# A314v1.net
KiCad netlist of a schematic drawn in EAGLE
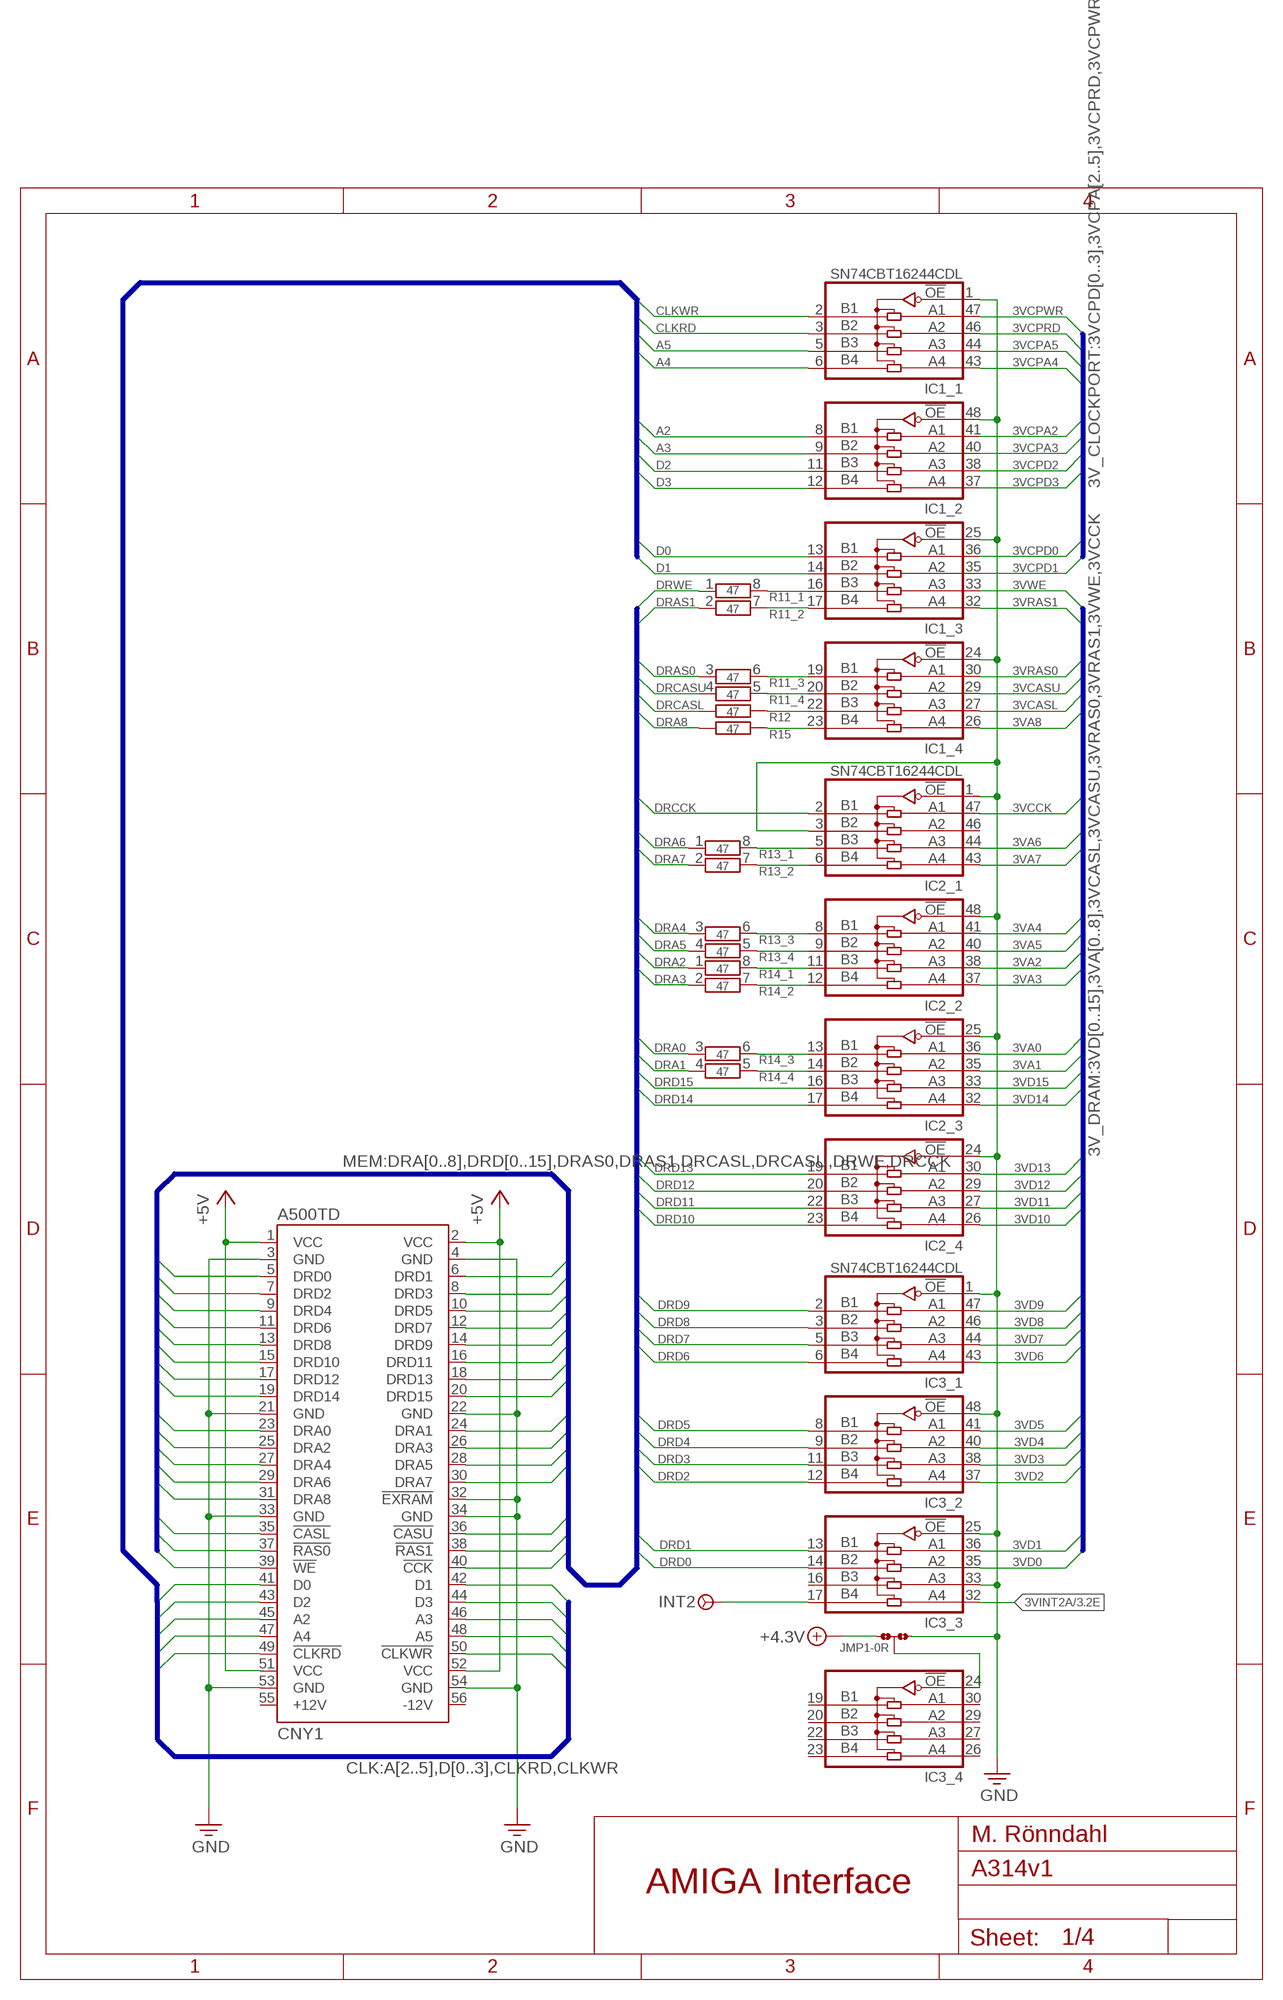
[diagram p0: schematic, sheet 1]
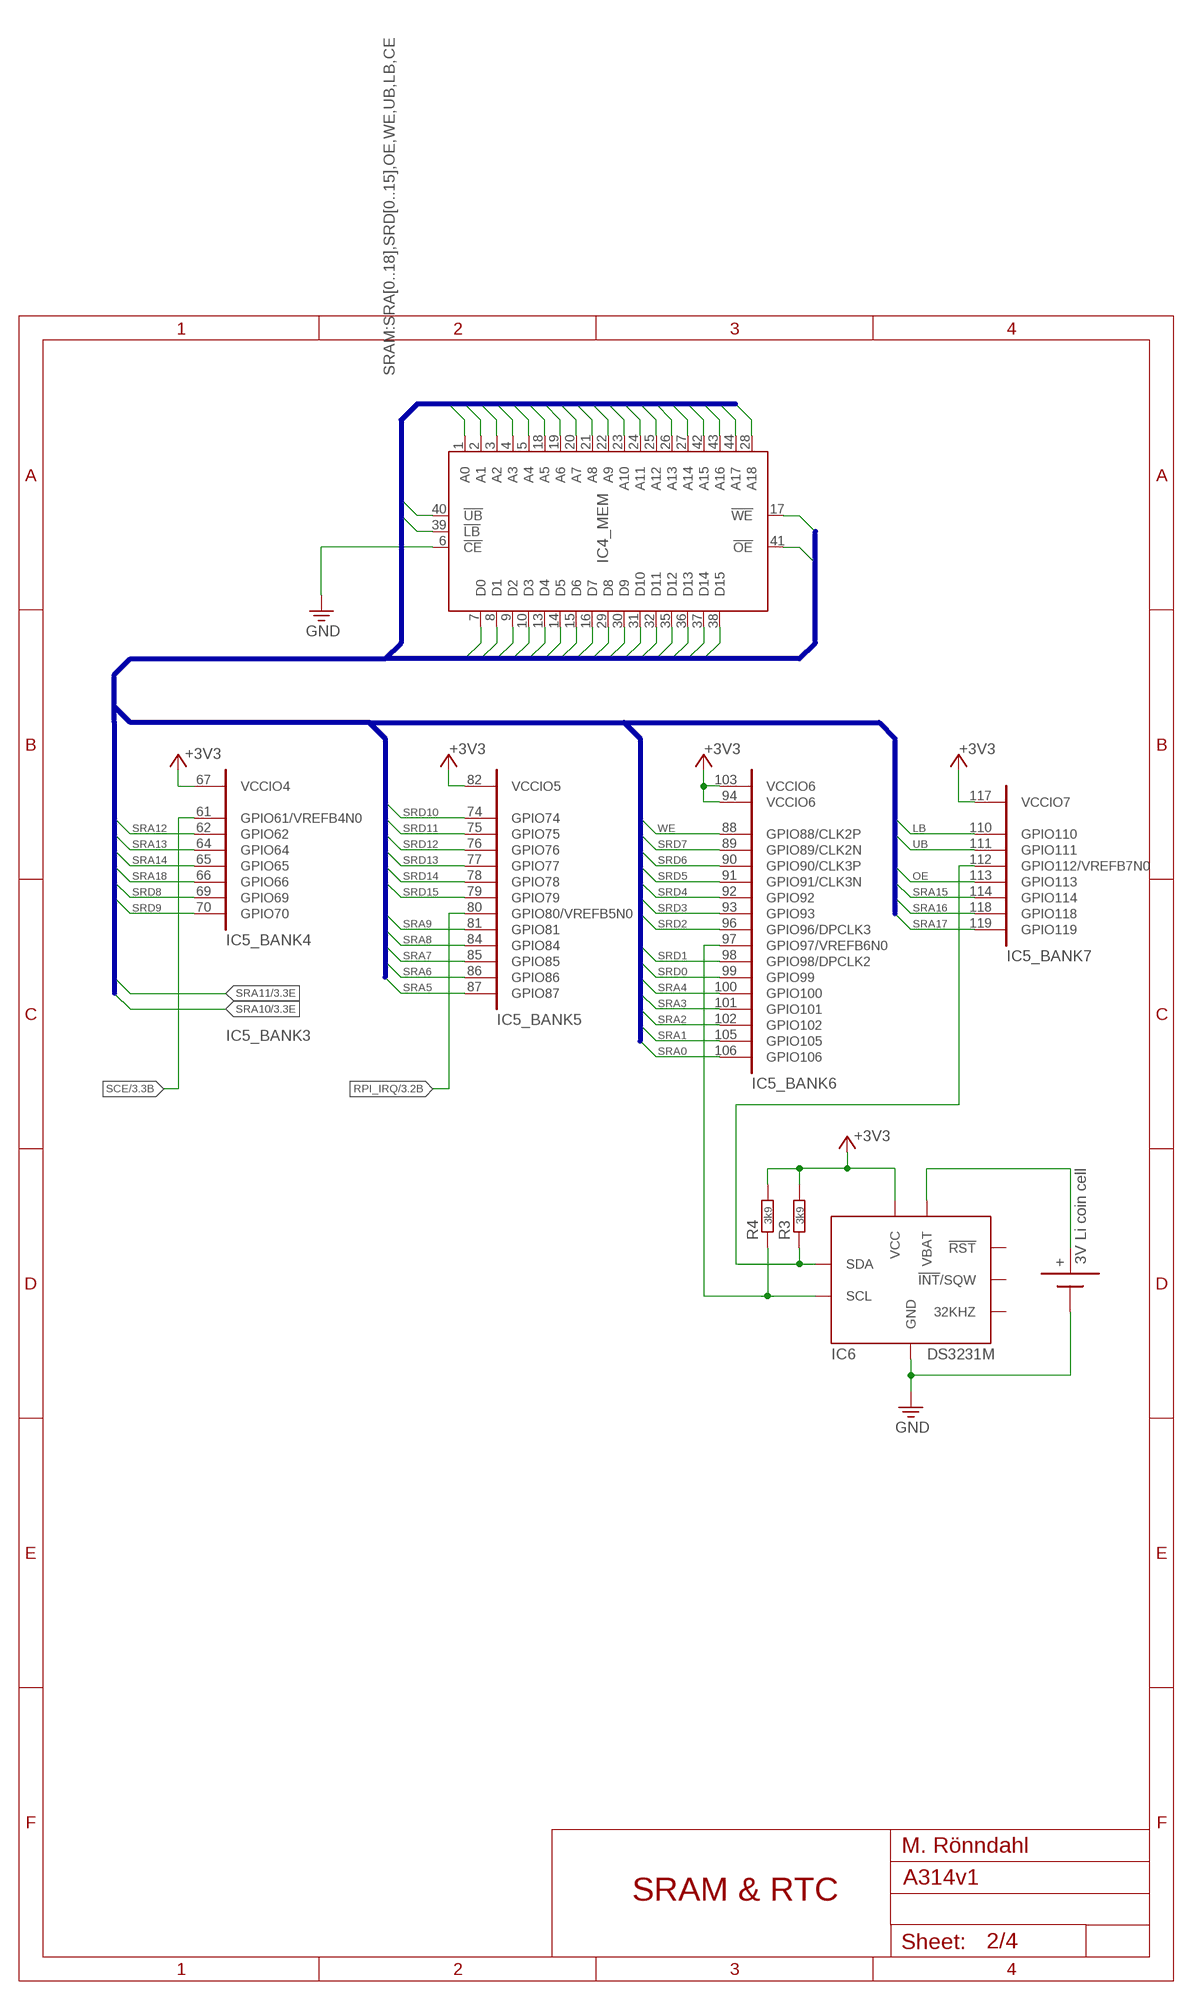
[diagram p1: schematic, sheet 2]
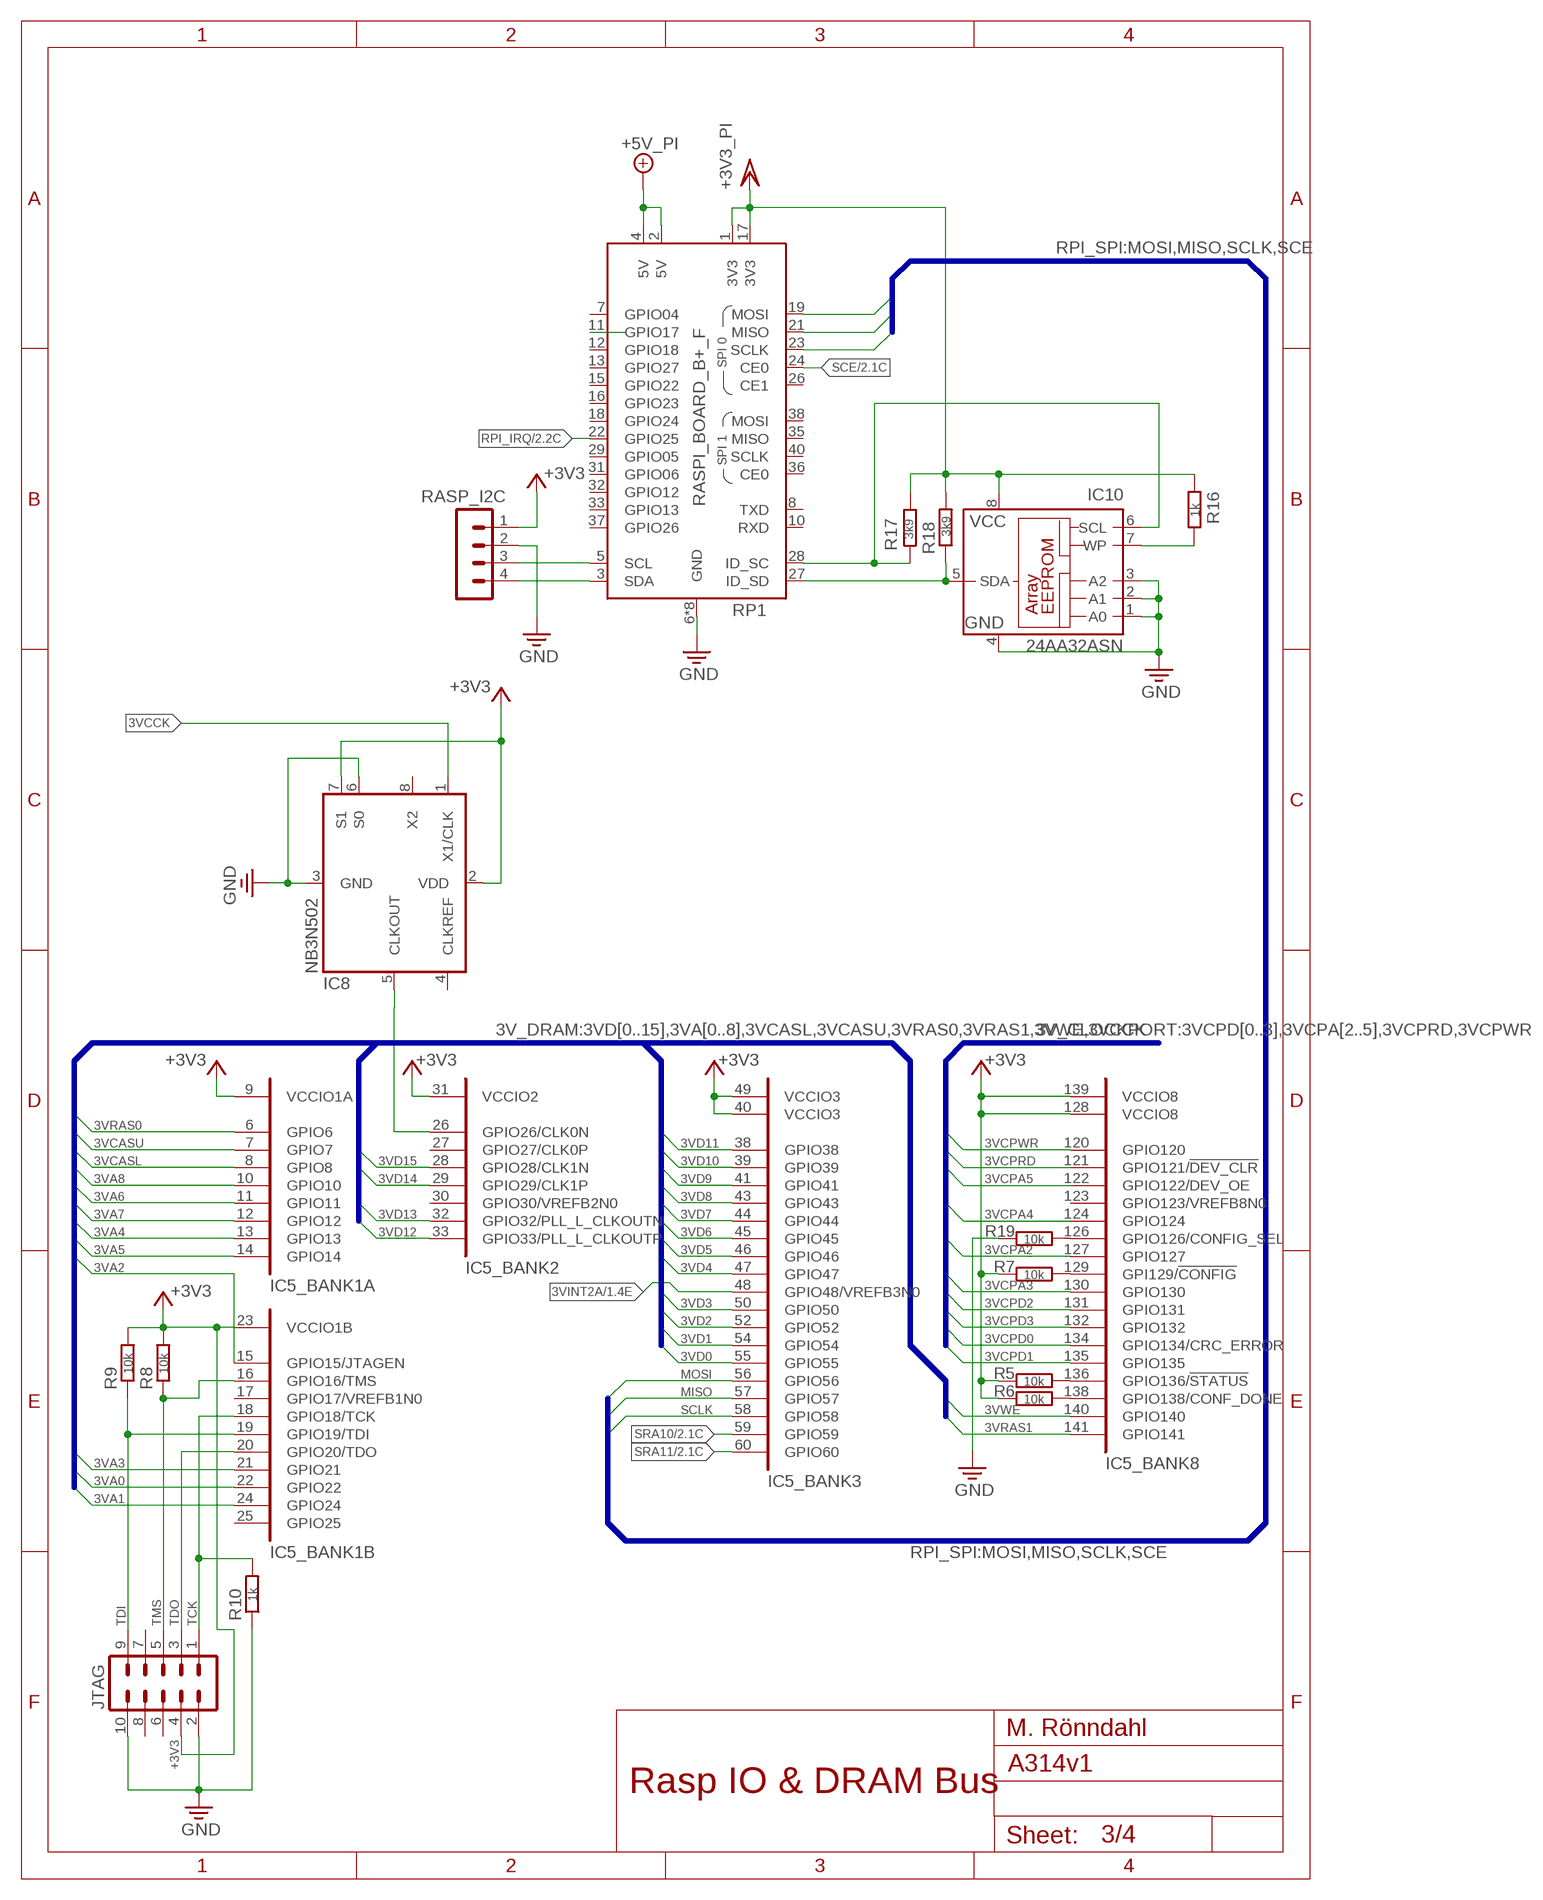
[diagram p2: schematic, sheet 3]
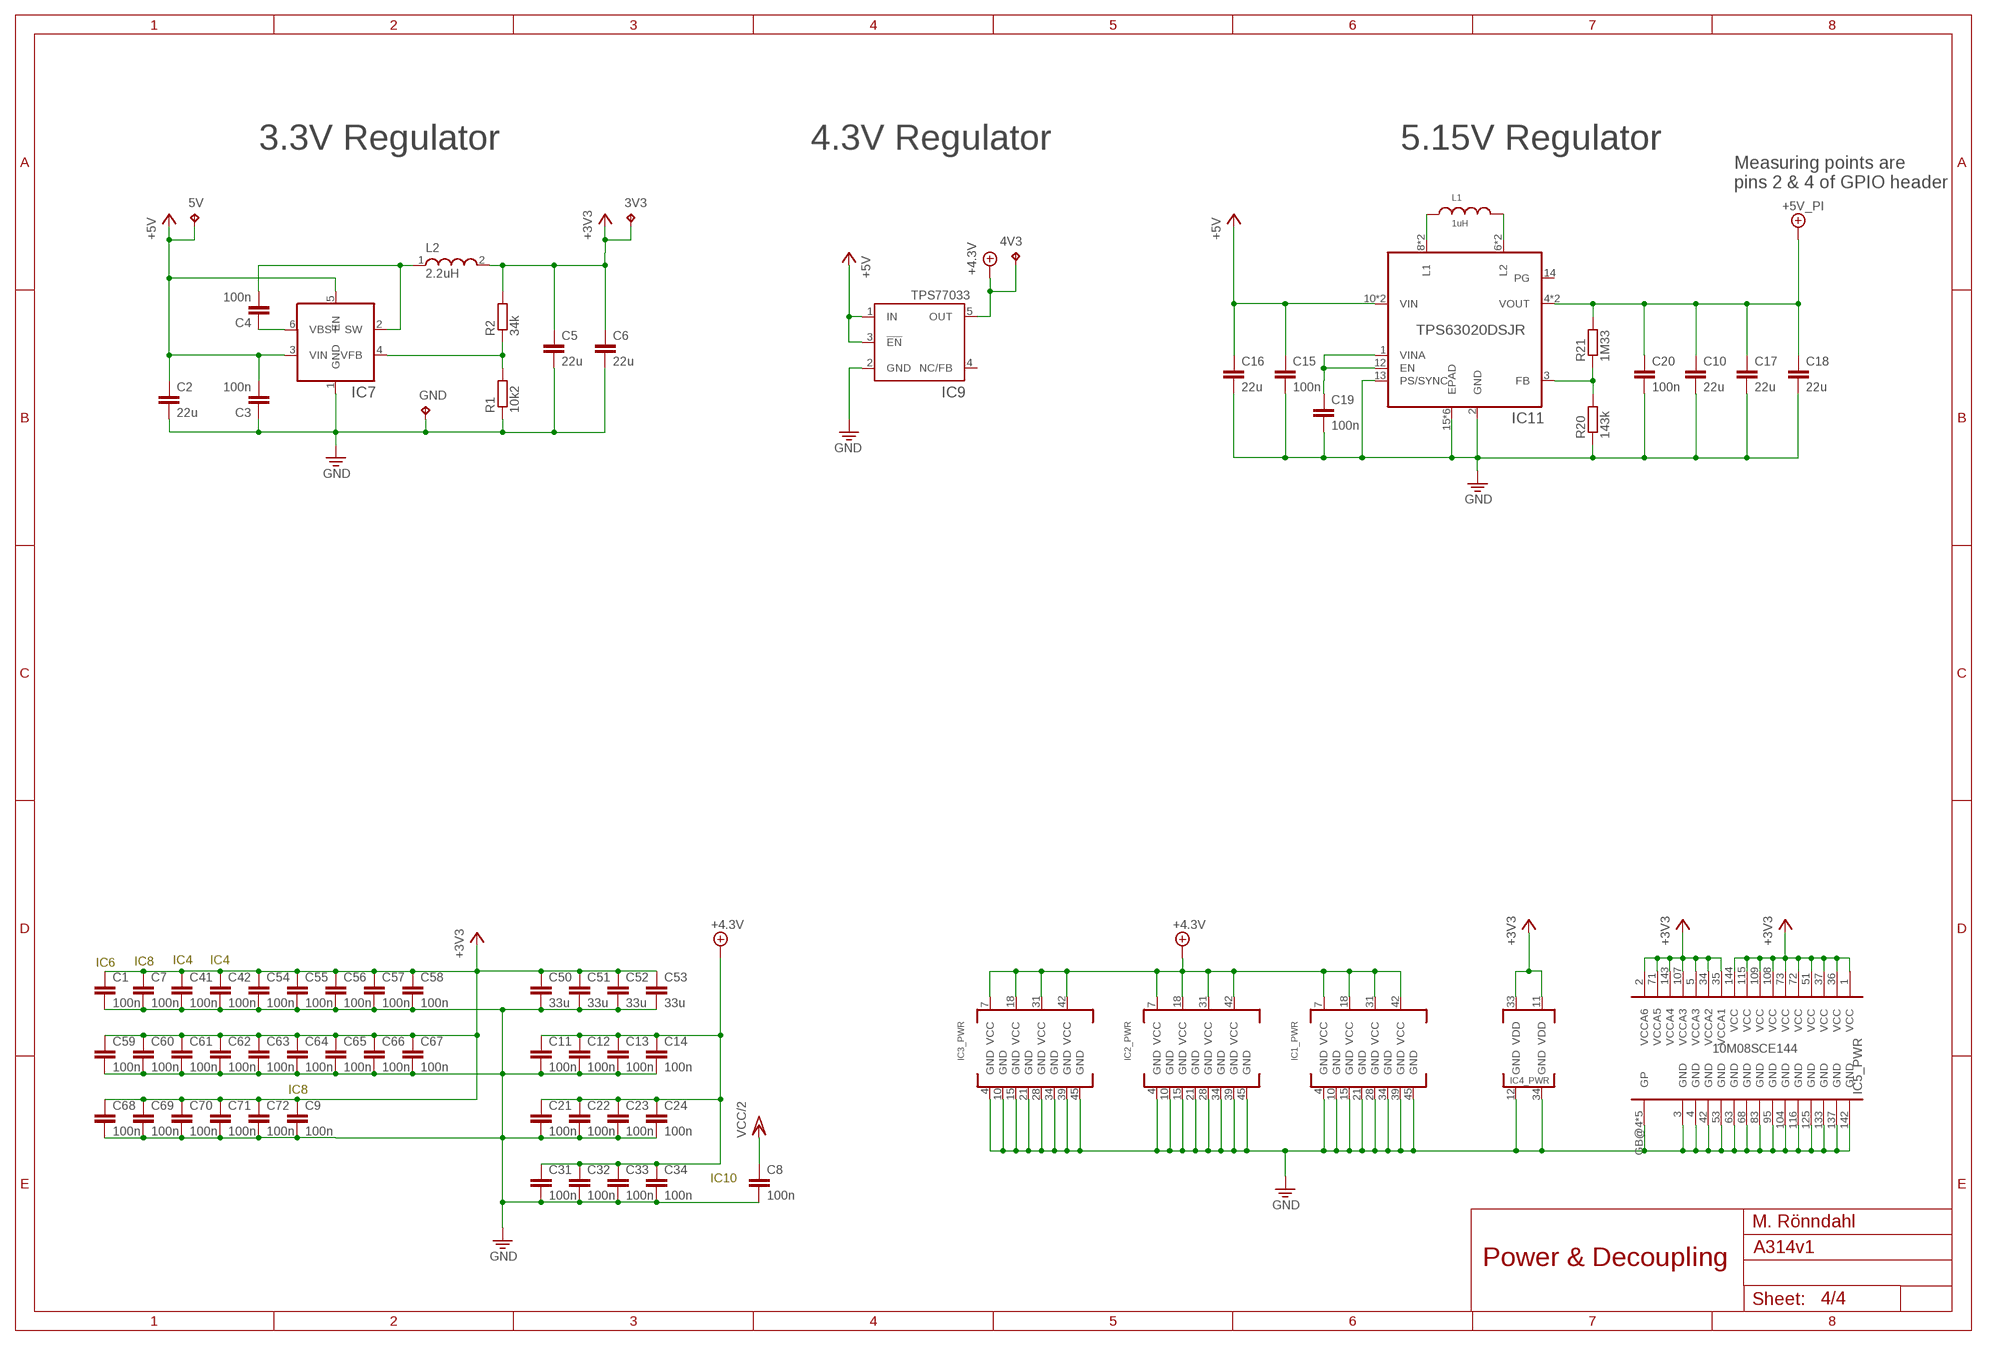
[diagram p3: schematic, sheet 4]

(export (version "E")
  (design (tool "Eeschema 10.0.6"))
  (components
    (comp (ref "CNY1")
      (value "A500TD")
      (footprint "eagle-import:TRAPDOOR")
      (libsource (lib "eagle-import") (part "A500TD"))
    )
    (comp (ref "IC1")
      (value "SN74CBT16244CDL")
      (footprint "eagle-import:SSOP-DL48")
      (libsource (lib "eagle-import") (part "SN74CBT16244CDL"))
    )
    (comp (ref "IC2")
      (value "SN74CBT16244CDL")
      (footprint "eagle-import:SSOP-DL48")
      (libsource (lib "eagle-import") (part "SN74CBT16244CDL"))
    )
    (comp (ref "IC3")
      (value "SN74CBT16244CDL")
      (footprint "eagle-import:SSOP-DL48")
      (libsource (lib "eagle-import") (part "SN74CBT16244CDL"))
    )
    (comp (ref "INT2")
      (value "TP1")
      (footprint "eagle-import:P1-08")
      (libsource (lib "eagle-import") (part "TP_LITE"))
    )
    (comp (ref "JMP1")
      (value "0R-JUMPC")
      (footprint "eagle-import:C0R-JMP")
      (libsource (lib "eagle-import") (part "0R-JUMPC"))
    )
    (comp (ref "R11")
      (value "47")
      (footprint "eagle-import:CTS742C083")
      (libsource (lib "eagle-import") (part "CTS742C083_S"))
    )
    (comp (ref "R12")
      (value "47")
      (footprint "eagle-import:R0805")
      (libsource (lib "eagle-import") (part "R-EU_R0805"))
    )
    (comp (ref "R13")
      (value "47")
      (footprint "eagle-import:CTS742C083")
      (libsource (lib "eagle-import") (part "CTS742C083_S"))
    )
    (comp (ref "R14")
      (value "47")
      (footprint "eagle-import:CTS742C083")
      (libsource (lib "eagle-import") (part "CTS742C083_S"))
    )
    (comp (ref "R15")
      (value "47")
      (footprint "eagle-import:R0805")
      (libsource (lib "eagle-import") (part "R-EU_R0805"))
    )
    (comp (ref "3V3")
      (value "TPPAD1-13")
      (footprint "eagle-import:P1-13")
      (libsource (lib "eagle-import") (part "TPPAD1-13"))
    )
    (comp (ref "4V3")
      (value "TPPAD1-13")
      (footprint "eagle-import:P1-13")
      (libsource (lib "eagle-import") (part "TPPAD1-13"))
    )
    (comp (ref "5V")
      (value "TPPAD1-13")
      (footprint "eagle-import:P1-13")
      (libsource (lib "eagle-import") (part "TPPAD1-13"))
    )
    (comp (ref "C1")
      (value "100n")
      (footprint "eagle-import:C0805")
      (libsource (lib "eagle-import") (part "C-EUC0805"))
    )
    (comp (ref "C2")
      (value "22u")
      (footprint "eagle-import:C1812K")
      (libsource (lib "eagle-import") (part "C-EUC1812K"))
    )
    (comp (ref "C3")
      (value "100n")
      (footprint "eagle-import:C0805")
      (libsource (lib "eagle-import") (part "C-EUC0805"))
    )
    (comp (ref "C4")
      (value "100n")
      (footprint "eagle-import:C0805")
      (libsource (lib "eagle-import") (part "C-EUC0805"))
    )
    (comp (ref "C5")
      (value "22u")
      (footprint "eagle-import:C1812K")
      (libsource (lib "eagle-import") (part "C-EUC1812K"))
    )
    (comp (ref "C6")
      (value "22u")
      (footprint "eagle-import:C1812K")
      (libsource (lib "eagle-import") (part "C-EUC1812K"))
    )
    (comp (ref "C7")
      (value "100n")
      (footprint "eagle-import:C0805")
      (libsource (lib "eagle-import") (part "C-EUC0805"))
    )
    (comp (ref "C8")
      (value "100n")
      (footprint "eagle-import:C0805")
      (libsource (lib "eagle-import") (part "C-EUC0805"))
    )
    (comp (ref "C9")
      (value "100n")
      (footprint "eagle-import:C0805")
      (libsource (lib "eagle-import") (part "C-EUC0805"))
    )
    (comp (ref "C10")
      (value "22u")
      (footprint "eagle-import:C1812K")
      (libsource (lib "eagle-import") (part "C-EUC1812K"))
    )
    (comp (ref "C11")
      (value "100n")
      (footprint "eagle-import:C0805")
      (libsource (lib "eagle-import") (part "C-EUC0805"))
    )
    (comp (ref "C12")
      (value "100n")
      (footprint "eagle-import:C0805")
      (libsource (lib "eagle-import") (part "C-EUC0805"))
    )
    (comp (ref "C13")
      (value "100n")
      (footprint "eagle-import:C0805")
      (libsource (lib "eagle-import") (part "C-EUC0805"))
    )
    (comp (ref "C14")
      (value "100n")
      (footprint "eagle-import:C0805")
      (libsource (lib "eagle-import") (part "C-EUC0805"))
    )
    (comp (ref "C15")
      (value "100n")
      (footprint "eagle-import:C0805")
      (libsource (lib "eagle-import") (part "C-EUC0805"))
    )
    (comp (ref "C16")
      (value "22u")
      (footprint "eagle-import:C1812K")
      (libsource (lib "eagle-import") (part "C-EUC1812K"))
    )
    (comp (ref "C17")
      (value "22u")
      (footprint "eagle-import:C1812K")
      (libsource (lib "eagle-import") (part "C-EUC1812K"))
    )
    (comp (ref "C18")
      (value "22u")
      (footprint "eagle-import:C1812K")
      (libsource (lib "eagle-import") (part "C-EUC1812K"))
    )
    (comp (ref "C19")
      (value "100n")
      (footprint "eagle-import:C0805")
      (libsource (lib "eagle-import") (part "C-EUC0805"))
    )
    (comp (ref "C20")
      (value "100n")
      (footprint "eagle-import:C0805")
      (libsource (lib "eagle-import") (part "C-EUC0805"))
    )
    (comp (ref "C21")
      (value "100n")
      (footprint "eagle-import:C0805")
      (libsource (lib "eagle-import") (part "C-EUC0805"))
    )
    (comp (ref "C22")
      (value "100n")
      (footprint "eagle-import:C0805")
      (libsource (lib "eagle-import") (part "C-EUC0805"))
    )
    (comp (ref "C23")
      (value "100n")
      (footprint "eagle-import:C0805")
      (libsource (lib "eagle-import") (part "C-EUC0805"))
    )
    (comp (ref "C24")
      (value "100n")
      (footprint "eagle-import:C0805")
      (libsource (lib "eagle-import") (part "C-EUC0805"))
    )
    (comp (ref "C31")
      (value "100n")
      (footprint "eagle-import:C0805")
      (libsource (lib "eagle-import") (part "C-EUC0805"))
    )
    (comp (ref "C32")
      (value "100n")
      (footprint "eagle-import:C0805")
      (libsource (lib "eagle-import") (part "C-EUC0805"))
    )
    (comp (ref "C33")
      (value "100n")
      (footprint "eagle-import:C0805")
      (libsource (lib "eagle-import") (part "C-EUC0805"))
    )
    (comp (ref "C34")
      (value "100n")
      (footprint "eagle-import:C0805")
      (libsource (lib "eagle-import") (part "C-EUC0805"))
    )
    (comp (ref "C41")
      (value "100n")
      (footprint "eagle-import:C0805")
      (libsource (lib "eagle-import") (part "C-EUC0805"))
    )
    (comp (ref "C42")
      (value "100n")
      (footprint "eagle-import:C0805")
      (libsource (lib "eagle-import") (part "C-EUC0805"))
    )
    (comp (ref "C50")
      (value "33u")
      (footprint "eagle-import:C0805")
      (libsource (lib "eagle-import") (part "C-EUC0805"))
    )
    (comp (ref "C51")
      (value "33u")
      (footprint "eagle-import:C0805")
      (libsource (lib "eagle-import") (part "C-EUC0805"))
    )
    (comp (ref "C52")
      (value "33u")
      (footprint "eagle-import:C0805")
      (libsource (lib "eagle-import") (part "C-EUC0805"))
    )
    (comp (ref "C53")
      (value "33u")
      (footprint "eagle-import:C0805")
      (libsource (lib "eagle-import") (part "C-EUC0805"))
    )
    (comp (ref "C54")
      (value "100n")
      (footprint "eagle-import:C0805")
      (libsource (lib "eagle-import") (part "C-EUC0805"))
    )
    (comp (ref "C55")
      (value "100n")
      (footprint "eagle-import:C0805")
      (libsource (lib "eagle-import") (part "C-EUC0805"))
    )
    (comp (ref "C56")
      (value "100n")
      (footprint "eagle-import:C0805")
      (libsource (lib "eagle-import") (part "C-EUC0805"))
    )
    (comp (ref "C57")
      (value "100n")
      (footprint "eagle-import:C0805")
      (libsource (lib "eagle-import") (part "C-EUC0805"))
    )
    (comp (ref "C58")
      (value "100n")
      (footprint "eagle-import:C0805")
      (libsource (lib "eagle-import") (part "C-EUC0805"))
    )
    (comp (ref "C59")
      (value "100n")
      (footprint "eagle-import:C0805")
      (libsource (lib "eagle-import") (part "C-EUC0805"))
    )
    (comp (ref "C60")
      (value "100n")
      (footprint "eagle-import:C0805")
      (libsource (lib "eagle-import") (part "C-EUC0805"))
    )
    (comp (ref "C61")
      (value "100n")
      (footprint "eagle-import:C0805")
      (libsource (lib "eagle-import") (part "C-EUC0805"))
    )
    (comp (ref "C62")
      (value "100n")
      (footprint "eagle-import:C0805")
      (libsource (lib "eagle-import") (part "C-EUC0805"))
    )
    (comp (ref "C63")
      (value "100n")
      (footprint "eagle-import:C0805")
      (libsource (lib "eagle-import") (part "C-EUC0805"))
    )
    (comp (ref "C64")
      (value "100n")
      (footprint "eagle-import:C0805")
      (libsource (lib "eagle-import") (part "C-EUC0805"))
    )
    (comp (ref "C65")
      (value "100n")
      (footprint "eagle-import:C0805")
      (libsource (lib "eagle-import") (part "C-EUC0805"))
    )
    (comp (ref "C66")
      (value "100n")
      (footprint "eagle-import:C0805")
      (libsource (lib "eagle-import") (part "C-EUC0805"))
    )
    (comp (ref "C67")
      (value "100n")
      (footprint "eagle-import:C0805")
      (libsource (lib "eagle-import") (part "C-EUC0805"))
    )
    (comp (ref "C68")
      (value "100n")
      (footprint "eagle-import:C0805")
      (libsource (lib "eagle-import") (part "C-EUC0805"))
    )
    (comp (ref "C69")
      (value "100n")
      (footprint "eagle-import:C0805")
      (libsource (lib "eagle-import") (part "C-EUC0805"))
    )
    (comp (ref "C70")
      (value "100n")
      (footprint "eagle-import:C0805")
      (libsource (lib "eagle-import") (part "C-EUC0805"))
    )
    (comp (ref "C71")
      (value "100n")
      (footprint "eagle-import:C0805")
      (libsource (lib "eagle-import") (part "C-EUC0805"))
    )
    (comp (ref "C72")
      (value "100n")
      (footprint "eagle-import:C0805")
      (libsource (lib "eagle-import") (part "C-EUC0805"))
    )
    (comp (ref "GND")
      (value "TPPAD1-13")
      (footprint "eagle-import:P1-13")
      (libsource (lib "eagle-import") (part "TPPAD1-13"))
    )
    (comp (ref "IC4")
      (value "IS61WV51216BLL-10TLI")
      (footprint "eagle-import:TSOP-2")
      (libsource (lib "eagle-import") (part "IS61WV51216BLL-10TLI"))
    )
    (comp (ref "IC5")
      (value "10M08SCE144")
      (footprint "eagle-import:SQFP-S-20X20-144")
      (libsource (lib "eagle-import") (part "10M08SCE144"))
    )
    (comp (ref "IC7")
      (value "TPS565208DDC")
      (footprint "eagle-import:THIN_SO23")
      (libsource (lib "eagle-import") (part "TPS565208DDC"))
    )
    (comp (ref "IC9")
      (value "TPS77033")
      (footprint "eagle-import:SOT23-DBV")
      (fields (field (name "MF") "TEXAS INSTRUMENTS") (field (name "MPN") "TPS77033DBVT"))
      (libsource (lib "eagle-import") (part "TPS77033"))
    )
    (comp (ref "IC11")
      (value "TPS63020DSJR")
      (footprint "eagle-import:DSJ14_2P85X1P58")
      (libsource (lib "eagle-import") (part "TPS63020DSJR"))
    )
    (comp (ref "L1")
      (value "1uH")
      (footprint "eagle-import:WE-TPC_6823")
      (libsource (lib "eagle-import") (part "WE-TPC_6823_744062001"))
    )
    (comp (ref "L2")
      (value "2.2uH")
      (footprint "eagle-import:WE-TPC_1028_1038")
      (libsource (lib "eagle-import") (part "WE-TPC_1028/1038"))
    )
    (comp (ref "R1")
      (value "10k2")
      (footprint "eagle-import:R0805")
      (libsource (lib "eagle-import") (part "R-EU_R0805"))
    )
    (comp (ref "R2")
      (value "34k")
      (footprint "eagle-import:R0805")
      (libsource (lib "eagle-import") (part "R-EU_R0805"))
    )
    (comp (ref "R20")
      (value "143k")
      (footprint "eagle-import:R0805")
      (libsource (lib "eagle-import") (part "R-EU_R0805"))
    )
    (comp (ref "R21")
      (value "1M33")
      (footprint "eagle-import:R0805")
      (libsource (lib "eagle-import") (part "R-EU_R0805"))
    )
    (comp (ref "BAT1")
      (value "CR2025/CR2032TH")
      (footprint "eagle-import:LINX20XX-THM")
      (libsource (lib "eagle-import") (part "CR2025/CR2032TH"))
    )
    (comp (ref "IC6")
      (value "DS3231M")
      (footprint "eagle-import:SOIC8")
      (libsource (lib "eagle-import") (part "DS3231M"))
    )
    (comp (ref "R3")
      (value "3k9")
      (footprint "eagle-import:R0805")
      (libsource (lib "eagle-import") (part "R-EU_R0805"))
    )
    (comp (ref "R4")
      (value "3k9")
      (footprint "eagle-import:R0805")
      (libsource (lib "eagle-import") (part "R-EU_R0805"))
    )
    (comp (ref "IC8")
      (value "NB3N502")
      (footprint "eagle-import:SO08")
      (libsource (lib "eagle-import") (part "NB3N502"))
    )
    (comp (ref "IC10")
      (value "24AA32ASN")
      (footprint "eagle-import:SO-08")
      (fields (field (name "MF") "MICROCHIP") (field (name "MPN") "24AA32A-I/SN"))
      (libsource (lib "eagle-import") (part "24SNAA32A"))
    )
    (comp (ref "JTAG")
      (value "MA05-2")
      (footprint "eagle-import:MA05-2")
      (libsource (lib "eagle-import") (part "MA05-2"))
    )
    (comp (ref "R5")
      (value "10k")
      (footprint "eagle-import:R0805")
      (libsource (lib "eagle-import") (part "R-EU_R0805"))
    )
    (comp (ref "R6")
      (value "10k")
      (footprint "eagle-import:R0805")
      (libsource (lib "eagle-import") (part "R-EU_R0805"))
    )
    (comp (ref "R7")
      (value "10k")
      (footprint "eagle-import:R0805")
      (libsource (lib "eagle-import") (part "R-EU_R0805"))
    )
    (comp (ref "R8")
      (value "10k")
      (footprint "eagle-import:R0805")
      (libsource (lib "eagle-import") (part "R-EU_R0805"))
    )
    (comp (ref "R9")
      (value "10k")
      (footprint "eagle-import:R0805")
      (libsource (lib "eagle-import") (part "R-EU_R0805"))
    )
    (comp (ref "R10")
      (value "1k")
      (footprint "eagle-import:R0805")
      (libsource (lib "eagle-import") (part "R-EU_R0805"))
    )
    (comp (ref "R16")
      (value "1k")
      (footprint "eagle-import:R0805")
      (libsource (lib "eagle-import") (part "R-EU_R0805"))
    )
    (comp (ref "R17")
      (value "3k9")
      (footprint "eagle-import:R0805")
      (libsource (lib "eagle-import") (part "R-EU_R0805"))
    )
    (comp (ref "R18")
      (value "3k9")
      (footprint "eagle-import:R0805")
      (libsource (lib "eagle-import") (part "R-EU_R0805"))
    )
    (comp (ref "R19")
      (value "10k")
      (footprint "eagle-import:R0805")
      (libsource (lib "eagle-import") (part "R-EU_R0805"))
    )
    (comp (ref "RASP_I2C")
      (value "MA04-1")
      (footprint "eagle-import:MA04-1")
      (libsource (lib "eagle-import") (part "MA04-1"))
    )
    (comp (ref "RP1")
      (value "RASPI_BOARD_B+_F")
      (footprint "eagle-import:RASPI_BOARD_B+_FULL")
      (libsource (lib "eagle-import") (part "RASPI_BOARD_B+_F"))
    )
  )
  (nets
    (net (code "3") (name "+3V3") (class "Default")
      (node (ref "3V3") (pin "TP") (pinfunction "TP_TP") (pintype "input"))
      (node (ref "C1") (pin "1") (pinfunction "1_1") (pintype "passive"))
      (node (ref "C41") (pin "1") (pinfunction "1_1") (pintype "passive"))
      (node (ref "C42") (pin "1") (pinfunction "1_1") (pintype "passive"))
      (node (ref "C5") (pin "1") (pinfunction "1_1") (pintype "passive"))
      (node (ref "C50") (pin "1") (pinfunction "1_1") (pintype "passive"))
      (node (ref "C51") (pin "1") (pinfunction "1_1") (pintype "passive"))
      (node (ref "C52") (pin "1") (pinfunction "1_1") (pintype "passive"))
      (node (ref "C53") (pin "1") (pinfunction "1_1") (pintype "passive"))
      (node (ref "C54") (pin "1") (pinfunction "1_1") (pintype "passive"))
      (node (ref "C55") (pin "1") (pinfunction "1_1") (pintype "passive"))
      (node (ref "C56") (pin "1") (pinfunction "1_1") (pintype "passive"))
      (node (ref "C57") (pin "1") (pinfunction "1_1") (pintype "passive"))
      (node (ref "C58") (pin "1") (pinfunction "1_1") (pintype "passive"))
      (node (ref "C59") (pin "1") (pinfunction "1_1") (pintype "passive"))
      (node (ref "C6") (pin "1") (pinfunction "1_1") (pintype "passive"))
      (node (ref "C60") (pin "1") (pinfunction "1_1") (pintype "passive"))
      (node (ref "C61") (pin "1") (pinfunction "1_1") (pintype "passive"))
      (node (ref "C62") (pin "1") (pinfunction "1_1") (pintype "passive"))
      (node (ref "C63") (pin "1") (pinfunction "1_1") (pintype "passive"))
      (node (ref "C64") (pin "1") (pinfunction "1_1") (pintype "passive"))
      (node (ref "C65") (pin "1") (pinfunction "1_1") (pintype "passive"))
      (node (ref "C66") (pin "1") (pinfunction "1_1") (pintype "passive"))
      (node (ref "C67") (pin "1") (pinfunction "1_1") (pintype "passive"))
      (node (ref "C68") (pin "1") (pinfunction "1_1") (pintype "passive"))
      (node (ref "C69") (pin "1") (pinfunction "1_1") (pintype "passive"))
      (node (ref "C7") (pin "1") (pinfunction "1_1") (pintype "passive"))
      (node (ref "C70") (pin "1") (pinfunction "1_1") (pintype "passive"))
      (node (ref "C71") (pin "1") (pinfunction "1_1") (pintype "passive"))
      (node (ref "C72") (pin "1") (pinfunction "1_1") (pintype "passive"))
      (node (ref "C9") (pin "1") (pinfunction "1_1") (pintype "passive"))
      (node (ref "IC4") (pin "11") (pinfunction "VDD_11") (pintype "bidirectional"))
      (node (ref "IC4") (pin "33") (pinfunction "VDD_33") (pintype "bidirectional"))
      (node (ref "IC5") (pin "1") (pinfunction "VCC_1") (pintype "power_in"))
      (node (ref "IC5") (pin "103") (pinfunction "VCCIO6_103") (pintype "power_in"))
      (node (ref "IC5") (pin "107") (pinfunction "VCCA3_107") (pintype "power_in"))
      (node (ref "IC5") (pin "108") (pinfunction "VCC_108") (pintype "power_in"))
      (node (ref "IC5") (pin "109") (pinfunction "VCC_109") (pintype "power_in"))
      (node (ref "IC5") (pin "115") (pinfunction "VCC_115") (pintype "power_in"))
      (node (ref "IC5") (pin "117") (pinfunction "VCCIO7_117") (pintype "power_in"))
      (node (ref "IC5") (pin "128") (pinfunction "VCCIO8_128") (pintype "power_in"))
      (node (ref "IC5") (pin "139") (pinfunction "VCCIO8_139") (pintype "power_in"))
      (node (ref "IC5") (pin "143") (pinfunction "VCCA4_143") (pintype "power_in"))
      (node (ref "IC5") (pin "144") (pinfunction "VCC_144") (pintype "power_in"))
      (node (ref "IC5") (pin "2") (pinfunction "VCCA6_2") (pintype "power_in"))
      (node (ref "IC5") (pin "23") (pinfunction "VCCIO1B_23") (pintype "power_in"))
      (node (ref "IC5") (pin "31") (pinfunction "VCCIO2_31") (pintype "power_in"))
      (node (ref "IC5") (pin "34") (pinfunction "VCCA2_34") (pintype "power_in"))
      (node (ref "IC5") (pin "35") (pinfunction "VCCA1_35") (pintype "power_in"))
      (node (ref "IC5") (pin "36") (pinfunction "VCC_36") (pintype "power_in"))
      (node (ref "IC5") (pin "37") (pinfunction "VCC_37") (pintype "power_in"))
      (node (ref "IC5") (pin "40") (pinfunction "VCCIO3_40") (pintype "power_in"))
      (node (ref "IC5") (pin "49") (pinfunction "VCCIO3_49") (pintype "power_in"))
      (node (ref "IC5") (pin "5") (pinfunction "VCCA3_5") (pintype "power_in"))
      (node (ref "IC5") (pin "51") (pinfunction "VCC_51") (pintype "power_in"))
      (node (ref "IC5") (pin "67") (pinfunction "VCCIO4_67") (pintype "power_in"))
      (node (ref "IC5") (pin "71") (pinfunction "VCCA5_71") (pintype "power_in"))
      (node (ref "IC5") (pin "72") (pinfunction "VCC_72") (pintype "power_in"))
      (node (ref "IC5") (pin "73") (pinfunction "VCC_73") (pintype "power_in"))
      (node (ref "IC5") (pin "82") (pinfunction "VCCIO5_82") (pintype "power_in"))
      (node (ref "IC5") (pin "9") (pinfunction "VCCIO1A_9") (pintype "power_in"))
      (node (ref "IC5") (pin "94") (pinfunction "VCCIO6_94") (pintype "power_in"))
      (node (ref "IC6") (pin "2") (pinfunction "VCC_2") (pintype "power_in"))
      (node (ref "IC8") (pin "2") (pinfunction "VDD_2") (pintype "power_in"))
      (node (ref "IC8") (pin "7") (pinfunction "S1_7") (pintype "input"))
      (node (ref "JTAG") (pin "4") (pinfunction "4_4") (pintype "passive"))
      (node (ref "L2") (pin "2") (pinfunction "2_2") (pintype "passive"))
      (node (ref "R2") (pin "2") (pinfunction "2_2") (pintype "passive"))
      (node (ref "R3") (pin "2") (pinfunction "2_2") (pintype "passive"))
      (node (ref "R4") (pin "2") (pinfunction "2_2") (pintype "passive"))
      (node (ref "R5") (pin "1") (pinfunction "1_1") (pintype "passive"))
      (node (ref "R6") (pin "1") (pinfunction "1_1") (pintype "passive"))
      (node (ref "R7") (pin "1") (pinfunction "1_1") (pintype "passive"))
      (node (ref "R8") (pin "2") (pinfunction "2_2") (pintype "passive"))
      (node (ref "R9") (pin "2") (pinfunction "2_2") (pintype "passive"))
      (node (ref "RASP_I2C") (pin "1") (pinfunction "1_1") (pintype "passive"))
    )
    (net (code "4") (name "+4.3V") (class "Default")
      (node (ref "4V3") (pin "TP") (pinfunction "TP_TP") (pintype "input"))
      (node (ref "C11") (pin "1") (pinfunction "1_1") (pintype "passive"))
      (node (ref "C12") (pin "1") (pinfunction "1_1") (pintype "passive"))
      (node (ref "C13") (pin "1") (pinfunction "1_1") (pintype "passive"))
      (node (ref "C14") (pin "1") (pinfunction "1_1") (pintype "passive"))
      (node (ref "C21") (pin "1") (pinfunction "1_1") (pintype "passive"))
      (node (ref "C22") (pin "1") (pinfunction "1_1") (pintype "passive"))
      (node (ref "C23") (pin "1") (pinfunction "1_1") (pintype "passive"))
      (node (ref "C24") (pin "1") (pinfunction "1_1") (pintype "passive"))
      (node (ref "C31") (pin "1") (pinfunction "1_1") (pintype "passive"))
      (node (ref "C32") (pin "1") (pinfunction "1_1") (pintype "passive"))
      (node (ref "C33") (pin "1") (pinfunction "1_1") (pintype "passive"))
      (node (ref "C34") (pin "1") (pinfunction "1_1") (pintype "passive"))
      (node (ref "IC1") (pin "18") (pinfunction "VCC_18") (pintype "power_in"))
      (node (ref "IC1") (pin "31") (pinfunction "VCC_31") (pintype "power_in"))
      (node (ref "IC1") (pin "42") (pinfunction "VCC_42") (pintype "power_in"))
      (node (ref "IC1") (pin "7") (pinfunction "VCC_7") (pintype "power_in"))
      (node (ref "IC2") (pin "18") (pinfunction "VCC_18") (pintype "power_in"))
      (node (ref "IC2") (pin "31") (pinfunction "VCC_31") (pintype "power_in"))
      (node (ref "IC2") (pin "42") (pinfunction "VCC_42") (pintype "power_in"))
      (node (ref "IC2") (pin "7") (pinfunction "VCC_7") (pintype "power_in"))
      (node (ref "IC3") (pin "18") (pinfunction "VCC_18") (pintype "power_in"))
      (node (ref "IC3") (pin "24") (pinfunction "~{OE}_24") (pintype "input"))
      (node (ref "IC3") (pin "31") (pinfunction "VCC_31") (pintype "power_in"))
      (node (ref "IC3") (pin "42") (pinfunction "VCC_42") (pintype "power_in"))
      (node (ref "IC3") (pin "7") (pinfunction "VCC_7") (pintype "power_in"))
      (node (ref "IC9") (pin "5") (pinfunction "OUT_5") (pintype "passive"))
      (node (ref "JMP1") (pin "1") (pinfunction "1_1") (pintype "passive"))
      (node (ref "JMP1") (pin "2") (pinfunction "2_2") (pintype "passive"))
    )
    (net (code "5") (name "+5V") (class "Default")
      (node (ref "5V") (pin "TP") (pinfunction "TP_TP") (pintype "input"))
      (node (ref "C15") (pin "2") (pinfunction "2_2") (pintype "passive"))
      (node (ref "C16") (pin "1") (pinfunction "1_1") (pintype "passive"))
      (node (ref "C2") (pin "1") (pinfunction "1_1") (pintype "passive"))
      (node (ref "C3") (pin "2") (pinfunction "2_2") (pintype "passive"))
      (node (ref "CNY1") (pin "1") (pinfunction "VCC_1") (pintype "power_in"))
      (node (ref "CNY1") (pin "2") (pinfunction "VCC_2") (pintype "power_in"))
      (node (ref "CNY1") (pin "51") (pinfunction "VCC_51") (pintype "power_in"))
      (node (ref "CNY1") (pin "52") (pinfunction "VCC_52") (pintype "power_in"))
      (node (ref "IC11") (pin "10") (pinfunction "VIN_10") (pintype "input"))
      (node (ref "IC11") (pin "11") (pinfunction "VIN_11") (pintype "input"))
      (node (ref "IC7") (pin "3") (pinfunction "VIN_3") (pintype "power_in"))
      (node (ref "IC7") (pin "5") (pinfunction "EN_5") (pintype "input"))
      (node (ref "IC9") (pin "1") (pinfunction "IN_1") (pintype "input"))
      (node (ref "IC9") (pin "3") (pinfunction "~{EN}_3") (pintype "input"))
    )
    (net (code "6") (name "+5V{slash}1") (class "Default")
      (node (ref "C10") (pin "1") (pinfunction "1_1") (pintype "passive"))
      (node (ref "C17") (pin "1") (pinfunction "1_1") (pintype "passive"))
      (node (ref "C18") (pin "1") (pinfunction "1_1") (pintype "passive"))
      (node (ref "C20") (pin "2") (pinfunction "2_2") (pintype "passive"))
      (node (ref "IC11") (pin "4") (pinfunction "VOUT_4") (pintype "output"))
      (node (ref "IC11") (pin "5") (pinfunction "VOUT_5") (pintype "output"))
      (node (ref "R21") (pin "2") (pinfunction "2_2") (pintype "passive"))
      (node (ref "RP1") (pin "2") (pinfunction "5V_2") (pintype "power_in"))
      (node (ref "RP1") (pin "4") (pinfunction "5V_4") (pintype "power_in"))
    )
    (net (code "7") (name "+12V") (class "Default")
      (node (ref "CNY1") (pin "55") (pinfunction "+12V_55") (pintype "power_in"))
    )
    (net (code "8") (name "-12V") (class "Default")
      (node (ref "CNY1") (pin "56") (pinfunction "-12V_56") (pintype "power_in"))
    )
    (net (code "17") (name "3VA0") (class "Default")
      (node (ref "IC2") (pin "36") (pinfunction "A1_36") (pintype "bidirectional"))
      (node (ref "IC5") (pin "22") (pinfunction "GPIO22_22") (pintype "bidirectional"))
    )
    (net (code "18") (name "3VA1") (class "Default")
      (node (ref "IC2") (pin "35") (pinfunction "A2_35") (pintype "bidirectional"))
      (node (ref "IC5") (pin "24") (pinfunction "GPIO24_24") (pintype "bidirectional"))
    )
    (net (code "19") (name "3VA2") (class "Default")
      (node (ref "IC2") (pin "38") (pinfunction "A3_38") (pintype "bidirectional"))
      (node (ref "IC5") (pin "15") (pinfunction "GPIO15/JTAGEN_15") (pintype "bidirectional"))
    )
    (net (code "20") (name "3VA3") (class "Default")
      (node (ref "IC2") (pin "37") (pinfunction "A4_37") (pintype "bidirectional"))
      (node (ref "IC5") (pin "21") (pinfunction "GPIO21_21") (pintype "bidirectional"))
    )
    (net (code "21") (name "3VA4") (class "Default")
      (node (ref "IC2") (pin "41") (pinfunction "A1_41") (pintype "bidirectional"))
      (node (ref "IC5") (pin "13") (pinfunction "GPIO13_13") (pintype "bidirectional"))
    )
    (net (code "22") (name "3VA5") (class "Default")
      (node (ref "IC2") (pin "40") (pinfunction "A2_40") (pintype "bidirectional"))
      (node (ref "IC5") (pin "14") (pinfunction "GPIO14_14") (pintype "bidirectional"))
    )
    (net (code "23") (name "3VA6") (class "Default")
      (node (ref "IC2") (pin "44") (pinfunction "A3_44") (pintype "bidirectional"))
      (node (ref "IC5") (pin "11") (pinfunction "GPIO11_11") (pintype "bidirectional"))
    )
    (net (code "24") (name "3VA7") (class "Default")
      (node (ref "IC2") (pin "43") (pinfunction "A4_43") (pintype "bidirectional"))
      (node (ref "IC5") (pin "12") (pinfunction "GPIO12_12") (pintype "bidirectional"))
    )
    (net (code "25") (name "3VA8") (class "Default")
      (node (ref "IC1") (pin "26") (pinfunction "A4_26") (pintype "bidirectional"))
      (node (ref "IC5") (pin "10") (pinfunction "GPIO10_10") (pintype "bidirectional"))
    )
    (net (code "26") (name "3VCASL") (class "Default")
      (node (ref "IC1") (pin "27") (pinfunction "A3_27") (pintype "bidirectional"))
      (node (ref "IC5") (pin "8") (pinfunction "GPIO8_8") (pintype "bidirectional"))
    )
    (net (code "27") (name "3VCASU") (class "Default")
      (node (ref "IC1") (pin "29") (pinfunction "A2_29") (pintype "bidirectional"))
      (node (ref "IC5") (pin "7") (pinfunction "GPIO7_7") (pintype "bidirectional"))
    )
    (net (code "28") (name "3VCCK") (class "Default")
      (node (ref "IC2") (pin "47") (pinfunction "A1_47") (pintype "bidirectional"))
      (node (ref "IC8") (pin "1") (pinfunction "X1/CLK_1") (pintype "input"))
    )
    (net (code "29") (name "3VCPA2") (class "Default")
      (node (ref "IC1") (pin "41") (pinfunction "A1_41") (pintype "bidirectional"))
      (node (ref "IC5") (pin "127") (pinfunction "GPIO127_127") (pintype "bidirectional"))
    )
    (net (code "30") (name "3VCPA3") (class "Default")
      (node (ref "IC1") (pin "40") (pinfunction "A2_40") (pintype "bidirectional"))
      (node (ref "IC5") (pin "130") (pinfunction "GPIO130_130") (pintype "bidirectional"))
    )
    (net (code "31") (name "3VCPA4") (class "Default")
      (node (ref "IC1") (pin "43") (pinfunction "A4_43") (pintype "bidirectional"))
      (node (ref "IC5") (pin "124") (pinfunction "GPIO124_124") (pintype "bidirectional"))
    )
    (net (code "32") (name "3VCPA5") (class "Default")
      (node (ref "IC1") (pin "44") (pinfunction "A3_44") (pintype "bidirectional"))
      (node (ref "IC5") (pin "122") (pinfunction "GPIO122/DEV_OE_122") (pintype "bidirectional"))
    )
    (net (code "33") (name "3VCPD0") (class "Default")
      (node (ref "IC1") (pin "36") (pinfunction "A1_36") (pintype "bidirectional"))
      (node (ref "IC5") (pin "134") (pinfunction "GPIO134/CRC_ERROR_134") (pintype "bidirectional"))
    )
    (net (code "34") (name "3VCPD1") (class "Default")
      (node (ref "IC1") (pin "35") (pinfunction "A2_35") (pintype "bidirectional"))
      (node (ref "IC5") (pin "135") (pinfunction "GPIO135_135") (pintype "bidirectional"))
    )
    (net (code "35") (name "3VCPD2") (class "Default")
      (node (ref "IC1") (pin "38") (pinfunction "A3_38") (pintype "bidirectional"))
      (node (ref "IC5") (pin "131") (pinfunction "GPIO131_131") (pintype "bidirectional"))
    )
    (net (code "36") (name "3VCPD3") (class "Default")
      (node (ref "IC1") (pin "37") (pinfunction "A4_37") (pintype "bidirectional"))
      (node (ref "IC5") (pin "132") (pinfunction "GPIO132_132") (pintype "bidirectional"))
    )
    (net (code "37") (name "3VCPRD") (class "Default")
      (node (ref "IC1") (pin "46") (pinfunction "A2_46") (pintype "bidirectional"))
      (node (ref "IC5") (pin "121") (pinfunction "GPIO121/~{DEV_CLR}_121") (pintype "bidirectional"))
    )
    (net (code "38") (name "3VCPWR") (class "Default")
      (node (ref "IC1") (pin "47") (pinfunction "A1_47") (pintype "bidirectional"))
      (node (ref "IC5") (pin "120") (pinfunction "GPIO120_120") (pintype "bidirectional"))
    )
    (net (code "39") (name "3VD0") (class "Default")
      (node (ref "IC3") (pin "35") (pinfunction "A2_35") (pintype "bidirectional"))
      (node (ref "IC5") (pin "55") (pinfunction "GPIO55_55") (pintype "bidirectional"))
    )
    (net (code "40") (name "3VD1") (class "Default")
      (node (ref "IC3") (pin "36") (pinfunction "A1_36") (pintype "bidirectional"))
      (node (ref "IC5") (pin "54") (pinfunction "GPIO54_54") (pintype "bidirectional"))
    )
    (net (code "41") (name "3VD2") (class "Default")
      (node (ref "IC3") (pin "37") (pinfunction "A4_37") (pintype "bidirectional"))
      (node (ref "IC5") (pin "52") (pinfunction "GPIO52_52") (pintype "bidirectional"))
    )
    (net (code "42") (name "3VD3") (class "Default")
      (node (ref "IC3") (pin "38") (pinfunction "A3_38") (pintype "bidirectional"))
      (node (ref "IC5") (pin "50") (pinfunction "GPIO50_50") (pintype "bidirectional"))
    )
    (net (code "43") (name "3VD4") (class "Default")
      (node (ref "IC3") (pin "40") (pinfunction "A2_40") (pintype "bidirectional"))
      (node (ref "IC5") (pin "47") (pinfunction "GPIO47_47") (pintype "bidirectional"))
    )
    (net (code "44") (name "3VD5") (class "Default")
      (node (ref "IC3") (pin "41") (pinfunction "A1_41") (pintype "bidirectional"))
      (node (ref "IC5") (pin "46") (pinfunction "GPIO46_46") (pintype "bidirectional"))
    )
    (net (code "45") (name "3VD6") (class "Default")
      (node (ref "IC3") (pin "43") (pinfunction "A4_43") (pintype "bidirectional"))
      (node (ref "IC5") (pin "45") (pinfunction "GPIO45_45") (pintype "bidirectional"))
    )
    (net (code "46") (name "3VD7") (class "Default")
      (node (ref "IC3") (pin "44") (pinfunction "A3_44") (pintype "bidirectional"))
      (node (ref "IC5") (pin "44") (pinfunction "GPIO44_44") (pintype "bidirectional"))
    )
    (net (code "47") (name "3VD8") (class "Default")
      (node (ref "IC3") (pin "46") (pinfunction "A2_46") (pintype "bidirectional"))
      (node (ref "IC5") (pin "43") (pinfunction "GPIO43_43") (pintype "bidirectional"))
    )
    (net (code "48") (name "3VD9") (class "Default")
      (node (ref "IC3") (pin "47") (pinfunction "A1_47") (pintype "bidirectional"))
      (node (ref "IC5") (pin "41") (pinfunction "GPIO41_41") (pintype "bidirectional"))
    )
    (net (code "49") (name "3VD10") (class "Default")
      (node (ref "IC2") (pin "26") (pinfunction "A4_26") (pintype "bidirectional"))
      (node (ref "IC5") (pin "39") (pinfunction "GPIO39_39") (pintype "bidirectional"))
    )
    (net (code "50") (name "3VD11") (class "Default")
      (node (ref "IC2") (pin "27") (pinfunction "A3_27") (pintype "bidirectional"))
      (node (ref "IC5") (pin "38") (pinfunction "GPIO38_38") (pintype "bidirectional"))
    )
    (net (code "51") (name "3VD12") (class "Default")
      (node (ref "IC2") (pin "29") (pinfunction "A2_29") (pintype "bidirectional"))
      (node (ref "IC5") (pin "33") (pinfunction "GPIO33/PLL_L_CLKOUTP_33") (pintype "bidirectional"))
    )
    (net (code "52") (name "3VD13") (class "Default")
      (node (ref "IC2") (pin "30") (pinfunction "A1_30") (pintype "bidirectional"))
      (node (ref "IC5") (pin "32") (pinfunction "GPIO32/PLL_L_CLKOUTN_32") (pintype "bidirectional"))
    )
    (net (code "53") (name "3VD14") (class "Default")
      (node (ref "IC2") (pin "32") (pinfunction "A4_32") (pintype "bidirectional"))
      (node (ref "IC5") (pin "29") (pinfunction "GPIO29/CLK1P_29") (pintype "bidirectional"))
    )
    (net (code "54") (name "3VD15") (class "Default")
      (node (ref "IC2") (pin "33") (pinfunction "A3_33") (pintype "bidirectional"))
      (node (ref "IC5") (pin "28") (pinfunction "GPIO28/CLK1N_28") (pintype "bidirectional"))
    )
    (net (code "55") (name "3VINT2A") (class "Default")
      (node (ref "IC3") (pin "32") (pinfunction "A4_32") (pintype "bidirectional"))
      (node (ref "IC5") (pin "48") (pinfunction "GPIO48/VREFB3N0_48") (pintype "bidirectional"))
    )
    (net (code "56") (name "3VRAS0") (class "Default")
      (node (ref "IC1") (pin "30") (pinfunction "A1_30") (pintype "bidirectional"))
      (node (ref "IC5") (pin "6") (pinfunction "GPIO6_6") (pintype "bidirectional"))
    )
    (net (code "57") (name "3VRAS1") (class "Default")
      (node (ref "IC1") (pin "32") (pinfunction "A4_32") (pintype "bidirectional"))
      (node (ref "IC5") (pin "141") (pinfunction "GPIO141_141") (pintype "bidirectional"))
    )
    (net (code "58") (name "3VWE") (class "Default")
      (node (ref "IC1") (pin "33") (pinfunction "A3_33") (pintype "bidirectional"))
      (node (ref "IC5") (pin "140") (pinfunction "GPIO140_140") (pintype "bidirectional"))
    )
    (net (code "59") (name "A2") (class "Default")
      (node (ref "CNY1") (pin "45") (pinfunction "A2_45") (pintype "output"))
      (node (ref "IC1") (pin "8") (pinfunction "B1_8") (pintype "bidirectional"))
    )
    (net (code "60") (name "A3") (class "Default")
      (node (ref "CNY1") (pin "46") (pinfunction "A3_46") (pintype "output"))
      (node (ref "IC1") (pin "9") (pinfunction "B2_9") (pintype "bidirectional"))
    )
    (net (code "61") (name "A4") (class "Default")
      (node (ref "CNY1") (pin "47") (pinfunction "A4_47") (pintype "output"))
      (node (ref "IC1") (pin "6") (pinfunction "B4_6") (pintype "bidirectional"))
    )
    (net (code "62") (name "A5") (class "Default")
      (node (ref "CNY1") (pin "48") (pinfunction "A5_48") (pintype "output"))
      (node (ref "IC1") (pin "5") (pinfunction "B3_5") (pintype "bidirectional"))
    )
    (net (code "63") (name "CLKRD") (class "Default")
      (node (ref "CNY1") (pin "49") (pinfunction "~{CLKRD}_49") (pintype "output"))
      (node (ref "IC1") (pin "3") (pinfunction "B2_3") (pintype "bidirectional"))
    )
    (net (code "64") (name "CLKWR") (class "Default")
      (node (ref "CNY1") (pin "50") (pinfunction "~{CLKWR}_50") (pintype "output"))
      (node (ref "IC1") (pin "2") (pinfunction "B1_2") (pintype "bidirectional"))
    )
    (net (code "65") (name "D0") (class "Default")
      (node (ref "CNY1") (pin "41") (pinfunction "D0_41") (pintype "bidirectional"))
      (node (ref "IC1") (pin "13") (pinfunction "B1_13") (pintype "bidirectional"))
    )
    (net (code "66") (name "D1") (class "Default")
      (node (ref "CNY1") (pin "42") (pinfunction "D1_42") (pintype "bidirectional"))
      (node (ref "IC1") (pin "14") (pinfunction "B2_14") (pintype "bidirectional"))
    )
    (net (code "67") (name "D2") (class "Default")
      (node (ref "CNY1") (pin "43") (pinfunction "D2_43") (pintype "bidirectional"))
      (node (ref "IC1") (pin "11") (pinfunction "B3_11") (pintype "bidirectional"))
    )
    (net (code "68") (name "D3") (class "Default")
      (node (ref "CNY1") (pin "44") (pinfunction "D3_44") (pintype "bidirectional"))
      (node (ref "IC1") (pin "12") (pinfunction "B4_12") (pintype "bidirectional"))
    )
    (net (code "69") (name "DRA0") (class "Default")
      (node (ref "CNY1") (pin "23") (pinfunction "DRA0_23") (pintype "output"))
      (node (ref "R14") (pin "3") (pinfunction "P$1_3") (pintype "passive"))
    )
    (net (code "70") (name "DRA1") (class "Default")
      (node (ref "CNY1") (pin "24") (pinfunction "DRA1_24") (pintype "output"))
      (node (ref "R14") (pin "4") (pinfunction "P$1_4") (pintype "passive"))
    )
    (net (code "71") (name "DRA2") (class "Default")
      (node (ref "CNY1") (pin "25") (pinfunction "DRA2_25") (pintype "output"))
      (node (ref "R14") (pin "1") (pinfunction "P$1_1") (pintype "passive"))
    )
    (net (code "72") (name "DRA3") (class "Default")
      (node (ref "CNY1") (pin "26") (pinfunction "DRA3_26") (pintype "output"))
      (node (ref "R14") (pin "2") (pinfunction "P$1_2") (pintype "passive"))
    )
    (net (code "73") (name "DRA4") (class "Default")
      (node (ref "CNY1") (pin "27") (pinfunction "DRA4_27") (pintype "output"))
      (node (ref "R13") (pin "3") (pinfunction "P$1_3") (pintype "passive"))
    )
    (net (code "74") (name "DRA5") (class "Default")
      (node (ref "CNY1") (pin "28") (pinfunction "DRA5_28") (pintype "output"))
      (node (ref "R13") (pin "4") (pinfunction "P$1_4") (pintype "passive"))
    )
    (net (code "75") (name "DRA6") (class "Default")
      (node (ref "CNY1") (pin "29") (pinfunction "DRA6_29") (pintype "output"))
      (node (ref "R13") (pin "1") (pinfunction "P$1_1") (pintype "passive"))
    )
    (net (code "76") (name "DRA7") (class "Default")
      (node (ref "CNY1") (pin "30") (pinfunction "DRA7_30") (pintype "output"))
      (node (ref "R13") (pin "2") (pinfunction "P$1_2") (pintype "passive"))
    )
    (net (code "77") (name "DRA8") (class "Default")
      (node (ref "CNY1") (pin "31") (pinfunction "DRA8_31") (pintype "output"))
      (node (ref "R15") (pin "2") (pinfunction "2_2") (pintype "passive"))
    )
    (net (code "78") (name "DRAS0") (class "Default")
      (node (ref "CNY1") (pin "37") (pinfunction "~{RAS0}_37") (pintype "output"))
      (node (ref "R11") (pin "3") (pinfunction "P$1_3") (pintype "passive"))
    )
    (net (code "79") (name "DRAS1") (class "Default")
      (node (ref "CNY1") (pin "38") (pinfunction "~{RAS1}_38") (pintype "output"))
      (node (ref "R11") (pin "2") (pinfunction "P$1_2") (pintype "passive"))
    )
    (net (code "80") (name "DRCASL") (class "Default")
      (node (ref "CNY1") (pin "35") (pinfunction "~{CASL}_35") (pintype "output"))
      (node (ref "R12") (pin "2") (pinfunction "2_2") (pintype "passive"))
    )
    (net (code "81") (name "DRCASU") (class "Default")
      (node (ref "CNY1") (pin "36") (pinfunction "~{CASU}_36") (pintype "output"))
      (node (ref "R11") (pin "4") (pinfunction "P$1_4") (pintype "passive"))
    )
    (net (code "82") (name "DRCCK") (class "Default")
      (node (ref "CNY1") (pin "40") (pinfunction "~{CCK}_40") (pintype "output"))
      (node (ref "IC2") (pin "2") (pinfunction "B1_2") (pintype "bidirectional"))
    )
    (net (code "83") (name "DRD0") (class "Default")
      (node (ref "CNY1") (pin "5") (pinfunction "DRD0_5") (pintype "bidirectional"))
      (node (ref "IC3") (pin "14") (pinfunction "B2_14") (pintype "bidirectional"))
    )
    (net (code "84") (name "DRD1") (class "Default")
      (node (ref "CNY1") (pin "6") (pinfunction "DRD1_6") (pintype "bidirectional"))
      (node (ref "IC3") (pin "13") (pinfunction "B1_13") (pintype "bidirectional"))
    )
    (net (code "85") (name "DRD2") (class "Default")
      (node (ref "CNY1") (pin "7") (pinfunction "DRD2_7") (pintype "bidirectional"))
      (node (ref "IC3") (pin "12") (pinfunction "B4_12") (pintype "bidirectional"))
    )
    (net (code "86") (name "DRD3") (class "Default")
      (node (ref "CNY1") (pin "8") (pinfunction "DRD3_8") (pintype "bidirectional"))
      (node (ref "IC3") (pin "11") (pinfunction "B3_11") (pintype "bidirectional"))
    )
    (net (code "87") (name "DRD4") (class "Default")
      (node (ref "CNY1") (pin "9") (pinfunction "DRD4_9") (pintype "bidirectional"))
      (node (ref "IC3") (pin "9") (pinfunction "B2_9") (pintype "bidirectional"))
    )
    (net (code "88") (name "DRD5") (class "Default")
      (node (ref "CNY1") (pin "10") (pinfunction "DRD5_10") (pintype "bidirectional"))
      (node (ref "IC3") (pin "8") (pinfunction "B1_8") (pintype "bidirectional"))
    )
    (net (code "89") (name "DRD6") (class "Default")
      (node (ref "CNY1") (pin "11") (pinfunction "DRD6_11") (pintype "bidirectional"))
      (node (ref "IC3") (pin "6") (pinfunction "B4_6") (pintype "bidirectional"))
    )
    (net (code "90") (name "DRD7") (class "Default")
      (node (ref "CNY1") (pin "12") (pinfunction "DRD7_12") (pintype "bidirectional"))
      (node (ref "IC3") (pin "5") (pinfunction "B3_5") (pintype "bidirectional"))
    )
    (net (code "91") (name "DRD8") (class "Default")
      (node (ref "CNY1") (pin "13") (pinfunction "DRD8_13") (pintype "bidirectional"))
      (node (ref "IC3") (pin "3") (pinfunction "B2_3") (pintype "bidirectional"))
    )
    (net (code "92") (name "DRD9") (class "Default")
      (node (ref "CNY1") (pin "14") (pinfunction "DRD9_14") (pintype "bidirectional"))
      (node (ref "IC3") (pin "2") (pinfunction "B1_2") (pintype "bidirectional"))
    )
    (net (code "93") (name "DRD10") (class "Default")
      (node (ref "CNY1") (pin "15") (pinfunction "DRD10_15") (pintype "bidirectional"))
      (node (ref "IC2") (pin "23") (pinfunction "B4_23") (pintype "bidirectional"))
    )
    (net (code "94") (name "DRD11") (class "Default")
      (node (ref "CNY1") (pin "16") (pinfunction "DRD11_16") (pintype "bidirectional"))
      (node (ref "IC2") (pin "22") (pinfunction "B3_22") (pintype "bidirectional"))
    )
    (net (code "95") (name "DRD12") (class "Default")
      (node (ref "CNY1") (pin "17") (pinfunction "DRD12_17") (pintype "bidirectional"))
      (node (ref "IC2") (pin "20") (pinfunction "B2_20") (pintype "bidirectional"))
    )
    (net (code "96") (name "DRD13") (class "Default")
      (node (ref "CNY1") (pin "18") (pinfunction "DRD13_18") (pintype "bidirectional"))
      (node (ref "IC2") (pin "19") (pinfunction "B1_19") (pintype "bidirectional"))
    )
    (net (code "97") (name "DRD14") (class "Default")
      (node (ref "CNY1") (pin "19") (pinfunction "DRD14_19") (pintype "bidirectional"))
      (node (ref "IC2") (pin "17") (pinfunction "B4_17") (pintype "bidirectional"))
    )
    (net (code "98") (name "DRD15") (class "Default")
      (node (ref "CNY1") (pin "20") (pinfunction "DRD15_20") (pintype "bidirectional"))
      (node (ref "IC2") (pin "16") (pinfunction "B3_16") (pintype "bidirectional"))
    )
    (net (code "99") (name "DRWE") (class "Default")
      (node (ref "CNY1") (pin "39") (pinfunction "~{WE}_39") (pintype "output"))
      (node (ref "R11") (pin "1") (pinfunction "P$1_1") (pintype "passive"))
    )
    (net (code "100") (name "GND") (class "Default")
      (node (ref "BAT1") (pin "GND") (pinfunction "-_GND") (pintype "power_in"))
      (node (ref "C1") (pin "2") (pinfunction "2_2") (pintype "passive"))
      (node (ref "C10") (pin "2") (pinfunction "2_2") (pintype "passive"))
      (node (ref "C11") (pin "2") (pinfunction "2_2") (pintype "passive"))
      (node (ref "C12") (pin "2") (pinfunction "2_2") (pintype "passive"))
      (node (ref "C13") (pin "2") (pinfunction "2_2") (pintype "passive"))
      (node (ref "C14") (pin "2") (pinfunction "2_2") (pintype "passive"))
      (node (ref "C15") (pin "1") (pinfunction "1_1") (pintype "passive"))
      (node (ref "C16") (pin "2") (pinfunction "2_2") (pintype "passive"))
      (node (ref "C17") (pin "2") (pinfunction "2_2") (pintype "passive"))
      (node (ref "C18") (pin "2") (pinfunction "2_2") (pintype "passive"))
      (node (ref "C19") (pin "1") (pinfunction "1_1") (pintype "passive"))
      (node (ref "C2") (pin "2") (pinfunction "2_2") (pintype "passive"))
      (node (ref "C20") (pin "1") (pinfunction "1_1") (pintype "passive"))
      (node (ref "C21") (pin "2") (pinfunction "2_2") (pintype "passive"))
      (node (ref "C22") (pin "2") (pinfunction "2_2") (pintype "passive"))
      (node (ref "C23") (pin "2") (pinfunction "2_2") (pintype "passive"))
      (node (ref "C24") (pin "2") (pinfunction "2_2") (pintype "passive"))
      (node (ref "C3") (pin "1") (pinfunction "1_1") (pintype "passive"))
      (node (ref "C31") (pin "2") (pinfunction "2_2") (pintype "passive"))
      (node (ref "C32") (pin "2") (pinfunction "2_2") (pintype "passive"))
      (node (ref "C33") (pin "2") (pinfunction "2_2") (pintype "passive"))
      (node (ref "C34") (pin "2") (pinfunction "2_2") (pintype "passive"))
      (node (ref "C41") (pin "2") (pinfunction "2_2") (pintype "passive"))
      (node (ref "C42") (pin "2") (pinfunction "2_2") (pintype "passive"))
      (node (ref "C5") (pin "2") (pinfunction "2_2") (pintype "passive"))
      (node (ref "C50") (pin "2") (pinfunction "2_2") (pintype "passive"))
      (node (ref "C51") (pin "2") (pinfunction "2_2") (pintype "passive"))
      (node (ref "C52") (pin "2") (pinfunction "2_2") (pintype "passive"))
      (node (ref "C53") (pin "2") (pinfunction "2_2") (pintype "passive"))
      (node (ref "C54") (pin "2") (pinfunction "2_2") (pintype "passive"))
      (node (ref "C55") (pin "2") (pinfunction "2_2") (pintype "passive"))
      (node (ref "C56") (pin "2") (pinfunction "2_2") (pintype "passive"))
      (node (ref "C57") (pin "2") (pinfunction "2_2") (pintype "passive"))
      (node (ref "C58") (pin "2") (pinfunction "2_2") (pintype "passive"))
      (node (ref "C59") (pin "2") (pinfunction "2_2") (pintype "passive"))
      (node (ref "C6") (pin "2") (pinfunction "2_2") (pintype "passive"))
      (node (ref "C60") (pin "2") (pinfunction "2_2") (pintype "passive"))
      (node (ref "C61") (pin "2") (pinfunction "2_2") (pintype "passive"))
      (node (ref "C62") (pin "2") (pinfunction "2_2") (pintype "passive"))
      (node (ref "C63") (pin "2") (pinfunction "2_2") (pintype "passive"))
      (node (ref "C64") (pin "2") (pinfunction "2_2") (pintype "passive"))
      (node (ref "C65") (pin "2") (pinfunction "2_2") (pintype "passive"))
      (node (ref "C66") (pin "2") (pinfunction "2_2") (pintype "passive"))
      (node (ref "C67") (pin "2") (pinfunction "2_2") (pintype "passive"))
      (node (ref "C68") (pin "2") (pinfunction "2_2") (pintype "passive"))
      (node (ref "C69") (pin "2") (pinfunction "2_2") (pintype "passive"))
      (node (ref "C7") (pin "2") (pinfunction "2_2") (pintype "passive"))
      (node (ref "C70") (pin "2") (pinfunction "2_2") (pintype "passive"))
      (node (ref "C71") (pin "2") (pinfunction "2_2") (pintype "passive"))
      (node (ref "C72") (pin "2") (pinfunction "2_2") (pintype "passive"))
      (node (ref "C8") (pin "2") (pinfunction "2_2") (pintype "passive"))
      (node (ref "C9") (pin "2") (pinfunction "2_2") (pintype "passive"))
      (node (ref "CNY1") (pin "21") (pinfunction "GND_21") (pintype "power_in"))
      (node (ref "CNY1") (pin "22") (pinfunction "GND_22") (pintype "power_in"))
      (node (ref "CNY1") (pin "3") (pinfunction "GND_3") (pintype "power_in"))
      (node (ref "CNY1") (pin "32") (pinfunction "~{EXRAM}_32") (pintype "input"))
      (node (ref "CNY1") (pin "33") (pinfunction "GND_33") (pintype "power_in"))
      (node (ref "CNY1") (pin "34") (pinfunction "GND_34") (pintype "power_in"))
      (node (ref "CNY1") (pin "4") (pinfunction "GND_4") (pintype "power_in"))
      (node (ref "CNY1") (pin "53") (pinfunction "GND_53") (pintype "power_in"))
      (node (ref "CNY1") (pin "54") (pinfunction "GND_54") (pintype "power_in"))
      (node (ref "GND") (pin "TP") (pinfunction "TP_TP") (pintype "input"))
      (node (ref "IC1") (pin "1") (pinfunction "~{OE}_1") (pintype "input"))
      (node (ref "IC1") (pin "10") (pinfunction "GND_10") (pintype "power_in"))
      (node (ref "IC1") (pin "15") (pinfunction "GND_15") (pintype "power_in"))
      (node (ref "IC1") (pin "21") (pinfunction "GND_21") (pintype "power_in"))
      (node (ref "IC1") (pin "24") (pinfunction "~{OE}_24") (pintype "input"))
      (node (ref "IC1") (pin "25") (pinfunction "~{OE}_25") (pintype "input"))
      (node (ref "IC1") (pin "28") (pinfunction "GND_28") (pintype "power_in"))
      (node (ref "IC1") (pin "34") (pinfunction "GND_34") (pintype "power_in"))
      (node (ref "IC1") (pin "39") (pinfunction "GND_39") (pintype "power_in"))
      (node (ref "IC1") (pin "4") (pinfunction "GND_4") (pintype "power_in"))
      (node (ref "IC1") (pin "45") (pinfunction "GND_45") (pintype "power_in"))
      (node (ref "IC1") (pin "48") (pinfunction "~{OE}_48") (pintype "input"))
      (node (ref "IC10") (pin "1") (pinfunction "A0_1") (pintype "input"))
      (node (ref "IC10") (pin "2") (pinfunction "A1_2") (pintype "input"))
      (node (ref "IC10") (pin "3") (pinfunction "A2_3") (pintype "input"))
      (node (ref "IC10") (pin "4") (pinfunction "GND_4") (pintype "power_in"))
      (node (ref "IC11") (pin "13") (pinfunction "PS/SYNC_13") (pintype "input"))
      (node (ref "IC11") (pin "15") (pinfunction "EPAD_15") (pintype "passive"))
      (node (ref "IC11") (pin "2") (pinfunction "GND_2") (pintype "power_in"))
      (node (ref "IC11") (pin "V_1") (pinfunction "EPAD_V_1") (pintype "passive"))
      (node (ref "IC11") (pin "V_2") (pinfunction "EPAD_V_2") (pintype "passive"))
      (node (ref "IC11") (pin "V_3") (pinfunction "EPAD_V_3") (pintype "passive"))
      (node (ref "IC11") (pin "V_4") (pinfunction "EPAD_V_4") (pintype "passive"))
      (node (ref "IC11") (pin "V_5") (pinfunction "EPAD_V_5") (pintype "passive"))
      (node (ref "IC2") (pin "1") (pinfunction "~{OE}_1") (pintype "input"))
      (node (ref "IC2") (pin "10") (pinfunction "GND_10") (pintype "power_in"))
      (node (ref "IC2") (pin "15") (pinfunction "GND_15") (pintype "power_in"))
      (node (ref "IC2") (pin "21") (pinfunction "GND_21") (pintype "power_in"))
      (node (ref "IC2") (pin "24") (pinfunction "~{OE}_24") (pintype "input"))
      (node (ref "IC2") (pin "25") (pinfunction "~{OE}_25") (pintype "input"))
      (node (ref "IC2") (pin "28") (pinfunction "GND_28") (pintype "power_in"))
      (node (ref "IC2") (pin "3") (pinfunction "B2_3") (pintype "bidirectional"))
      (node (ref "IC2") (pin "34") (pinfunction "GND_34") (pintype "power_in"))
      (node (ref "IC2") (pin "39") (pinfunction "GND_39") (pintype "power_in"))
      (node (ref "IC2") (pin "4") (pinfunction "GND_4") (pintype "power_in"))
      (node (ref "IC2") (pin "45") (pinfunction "GND_45") (pintype "power_in"))
      (node (ref "IC2") (pin "48") (pinfunction "~{OE}_48") (pintype "input"))
      (node (ref "IC3") (pin "1") (pinfunction "~{OE}_1") (pintype "input"))
      (node (ref "IC3") (pin "10") (pinfunction "GND_10") (pintype "power_in"))
      (node (ref "IC3") (pin "15") (pinfunction "GND_15") (pintype "power_in"))
      (node (ref "IC3") (pin "21") (pinfunction "GND_21") (pintype "power_in"))
      (node (ref "IC3") (pin "25") (pinfunction "~{OE}_25") (pintype "input"))
      (node (ref "IC3") (pin "28") (pinfunction "GND_28") (pintype "power_in"))
      (node (ref "IC3") (pin "33") (pinfunction "A3_33") (pintype "bidirectional"))
      (node (ref "IC3") (pin "34") (pinfunction "GND_34") (pintype "power_in"))
      (node (ref "IC3") (pin "39") (pinfunction "GND_39") (pintype "power_in"))
      (node (ref "IC3") (pin "4") (pinfunction "GND_4") (pintype "power_in"))
      (node (ref "IC3") (pin "45") (pinfunction "GND_45") (pintype "power_in"))
      (node (ref "IC3") (pin "48") (pinfunction "~{OE}_48") (pintype "input"))
      (node (ref "IC4") (pin "12") (pinfunction "GND_12") (pintype "bidirectional"))
      (node (ref "IC4") (pin "34") (pinfunction "GND_34") (pintype "bidirectional"))
      (node (ref "IC4") (pin "6") (pinfunction "~{CE}_6") (pintype "input"))
      (node (ref "IC5") (pin "104") (pinfunction "GND_104") (pintype "power_in"))
      (node (ref "IC5") (pin "116") (pinfunction "GND_116") (pintype "power_in"))
      (node (ref "IC5") (pin "125") (pinfunction "GND_125") (pintype "power_in"))
      (node (ref "IC5") (pin "133") (pinfunction "GND_133") (pintype "power_in"))
      (node (ref "IC5") (pin "137") (pinfunction "GND_137") (pintype "power_in"))
      (node (ref "IC5") (pin "142") (pinfunction "GND_142") (pintype "power_in"))
      (node (ref "IC5") (pin "3") (pinfunction "GND_3") (pintype "power_in"))
      (node (ref "IC5") (pin "4") (pinfunction "GND_4") (pintype "power_in"))
      (node (ref "IC5") (pin "42") (pinfunction "GND_42") (pintype "power_in"))
      (node (ref "IC5") (pin "53") (pinfunction "GND_53") (pintype "power_in"))
      (node (ref "IC5") (pin "63") (pinfunction "GND_63") (pintype "power_in"))
      (node (ref "IC5") (pin "68") (pinfunction "GND_68") (pintype "power_in"))
      (node (ref "IC5") (pin "83") (pinfunction "GND_83") (pintype "power_in"))
      (node (ref "IC5") (pin "95") (pinfunction "GND_95") (pintype "power_in"))
      (node (ref "IC5") (pin "GB@4") (pinfunction "GP_GB@4") (pintype "power_in"))
      (node (ref "IC5") (pin "GP@1") (pinfunction "GP_GP@1") (pintype "power_in"))
      (node (ref "IC5") (pin "GP@2") (pinfunction "GP_GP@2") (pintype "power_in"))
      (node (ref "IC5") (pin "GP@3") (pinfunction "GP_GP@3") (pintype "power_in"))
      (node (ref "IC5") (pin "GP@5") (pinfunction "GP_GP@5") (pintype "power_in"))
      (node (ref "IC6") (pin "5") (pinfunction "GND_5") (pintype "power_in"))
      (node (ref "IC7") (pin "1") (pinfunction "GND_1") (pintype "power_in"))
      (node (ref "IC8") (pin "3") (pinfunction "GND_3") (pintype "power_in"))
      (node (ref "IC8") (pin "6") (pinfunction "S0_6") (pintype "input"))
      (node (ref "IC9") (pin "2") (pinfunction "GND_2") (pintype "power_in"))
      (node (ref "JMP1") (pin "3") (pinfunction "3_3") (pintype "passive"))
      (node (ref "JTAG") (pin "10") (pinfunction "10_10") (pintype "passive"))
      (node (ref "JTAG") (pin "2") (pinfunction "2_2") (pintype "passive"))
      (node (ref "R1") (pin "1") (pinfunction "1_1") (pintype "passive"))
      (node (ref "R10") (pin "1") (pinfunction "1_1") (pintype "passive"))
      (node (ref "R19") (pin "1") (pinfunction "1_1") (pintype "passive"))
      (node (ref "R20") (pin "1") (pinfunction "1_1") (pintype "passive"))
      (node (ref "RASP_I2C") (pin "2") (pinfunction "2_2") (pintype "passive"))
      (node (ref "RP1") (pin "14") (pinfunction "GND_14") (pintype "power_in"))
      (node (ref "RP1") (pin "20") (pinfunction "GND_20") (pintype "power_in"))
      (node (ref "RP1") (pin "25") (pinfunction "GND_25") (pintype "power_in"))
      (node (ref "RP1") (pin "30") (pinfunction "GND_30") (pintype "power_in"))
      (node (ref "RP1") (pin "34") (pinfunction "GND_34") (pintype "power_in"))
      (node (ref "RP1") (pin "39") (pinfunction "GND_39") (pintype "power_in"))
      (node (ref "RP1") (pin "6") (pinfunction "GND_6") (pintype "power_in"))
      (node (ref "RP1") (pin "9") (pinfunction "GND_9") (pintype "power_in"))
    )
    (net (code "101") (name "LB") (class "Default")
      (node (ref "IC4") (pin "39") (pinfunction "~{LB}_39") (pintype "input"))
      (node (ref "IC5") (pin "110") (pinfunction "GPIO110_110") (pintype "bidirectional"))
    )
    (net (code "102") (name "MISO") (class "Default")
      (node (ref "IC5") (pin "57") (pinfunction "GPIO57_57") (pintype "bidirectional"))
      (node (ref "RP1") (pin "21") (pinfunction "MISO_21") (pintype "bidirectional"))
    )
    (net (code "103") (name "MOSI") (class "Default")
      (node (ref "IC5") (pin "56") (pinfunction "GPIO56_56") (pintype "bidirectional"))
      (node (ref "RP1") (pin "19") (pinfunction "MOSI_19") (pintype "bidirectional"))
    )
    (net (code "104") (name "Net-(IC1C-B3)") (class "Default")
      (node (ref "IC1") (pin "16") (pinfunction "B3_16") (pintype "bidirectional"))
      (node (ref "R11") (pin "8") (pinfunction "P$2_8") (pintype "passive"))
    )
    (net (code "105") (name "Net-(IC1C-B4)") (class "Default")
      (node (ref "IC1") (pin "17") (pinfunction "B4_17") (pintype "bidirectional"))
      (node (ref "R11") (pin "7") (pinfunction "P$2_7") (pintype "passive"))
    )
    (net (code "106") (name "Net-(IC1D-B1)") (class "Default")
      (node (ref "IC1") (pin "19") (pinfunction "B1_19") (pintype "bidirectional"))
      (node (ref "R11") (pin "6") (pinfunction "P$2_6") (pintype "passive"))
    )
    (net (code "107") (name "Net-(IC1D-B2)") (class "Default")
      (node (ref "IC1") (pin "20") (pinfunction "B2_20") (pintype "bidirectional"))
      (node (ref "R11") (pin "5") (pinfunction "P$2_5") (pintype "passive"))
    )
    (net (code "108") (name "Net-(IC1D-B3)") (class "Default")
      (node (ref "IC1") (pin "22") (pinfunction "B3_22") (pintype "bidirectional"))
      (node (ref "R12") (pin "1") (pinfunction "1_1") (pintype "passive"))
    )
    (net (code "109") (name "Net-(IC1D-B4)") (class "Default")
      (node (ref "IC1") (pin "23") (pinfunction "B4_23") (pintype "bidirectional"))
      (node (ref "R15") (pin "1") (pinfunction "1_1") (pintype "passive"))
    )
    (net (code "110") (name "Net-(IC2A-B3)") (class "Default")
      (node (ref "IC2") (pin "5") (pinfunction "B3_5") (pintype "bidirectional"))
      (node (ref "R13") (pin "8") (pinfunction "P$2_8") (pintype "passive"))
    )
    (net (code "111") (name "Net-(IC2A-B4)") (class "Default")
      (node (ref "IC2") (pin "6") (pinfunction "B4_6") (pintype "bidirectional"))
      (node (ref "R13") (pin "7") (pinfunction "P$2_7") (pintype "passive"))
    )
    (net (code "112") (name "Net-(IC2B-B1)") (class "Default")
      (node (ref "IC2") (pin "8") (pinfunction "B1_8") (pintype "bidirectional"))
      (node (ref "R13") (pin "6") (pinfunction "P$2_6") (pintype "passive"))
    )
    (net (code "113") (name "Net-(IC2B-B2)") (class "Default")
      (node (ref "IC2") (pin "9") (pinfunction "B2_9") (pintype "bidirectional"))
      (node (ref "R13") (pin "5") (pinfunction "P$2_5") (pintype "passive"))
    )
    (net (code "114") (name "Net-(IC2B-B3)") (class "Default")
      (node (ref "IC2") (pin "11") (pinfunction "B3_11") (pintype "bidirectional"))
      (node (ref "R14") (pin "8") (pinfunction "P$2_8") (pintype "passive"))
    )
    (net (code "115") (name "Net-(IC2B-B4)") (class "Default")
      (node (ref "IC2") (pin "12") (pinfunction "B4_12") (pintype "bidirectional"))
      (node (ref "R14") (pin "7") (pinfunction "P$2_7") (pintype "passive"))
    )
    (net (code "116") (name "Net-(IC2C-B1)") (class "Default")
      (node (ref "IC2") (pin "13") (pinfunction "B1_13") (pintype "bidirectional"))
      (node (ref "R14") (pin "6") (pinfunction "P$2_6") (pintype "passive"))
    )
    (net (code "117") (name "Net-(IC2C-B2)") (class "Default")
      (node (ref "IC2") (pin "14") (pinfunction "B2_14") (pintype "bidirectional"))
      (node (ref "R14") (pin "5") (pinfunction "P$2_5") (pintype "passive"))
    )
    (net (code "118") (name "Net-(IC3C-B4)") (class "Default")
      (node (ref "IC3") (pin "17") (pinfunction "B4_17") (pintype "bidirectional"))
      (node (ref "INT2") (pin "TP") (pinfunction "TP_TP") (pintype "bidirectional"))
    )
    (net (code "119") (name "Net-(IC5C-GPIO26{slash}CLK0N)") (class "Default")
      (node (ref "IC5") (pin "26") (pinfunction "GPIO26/CLK0N_26") (pintype "bidirectional"))
      (node (ref "IC8") (pin "5") (pinfunction "CLKOUT_5") (pintype "output"))
    )
    (net (code "120") (name "Net-(IC5G-GPIO97{slash}VREFB6N0)") (class "Default")
      (node (ref "IC5") (pin "97") (pinfunction "GPIO97/VREFB6N0_97") (pintype "bidirectional"))
      (node (ref "IC6") (pin "8") (pinfunction "SCL_8") (pintype "input"))
      (node (ref "R4") (pin "1") (pinfunction "1_1") (pintype "passive"))
    )
    (net (code "121") (name "Net-(IC5H-GPIO112{slash}VREFB7N0)") (class "Default")
      (node (ref "IC5") (pin "112") (pinfunction "GPIO112/VREFB7N0_112") (pintype "bidirectional"))
      (node (ref "IC6") (pin "7") (pinfunction "SDA_7") (pintype "bidirectional"))
      (node (ref "R3") (pin "1") (pinfunction "1_1") (pintype "passive"))
    )
    (net (code "122") (name "Net-(IC5I-GPI129{slash}~{CONFIG})") (class "Default")
      (node (ref "IC5") (pin "129") (pinfunction "GPI129/~{CONFIG}_129") (pintype "input"))
      (node (ref "R7") (pin "2") (pinfunction "2_2") (pintype "passive"))
    )
    (net (code "123") (name "Net-(IC5I-GPIO126{slash}CONFIG_SEL)") (class "Default")
      (node (ref "IC5") (pin "126") (pinfunction "GPIO126/CONFIG_SEL_126") (pintype "bidirectional"))
      (node (ref "R19") (pin "2") (pinfunction "2_2") (pintype "passive"))
    )
    (net (code "124") (name "Net-(IC5I-GPIO136{slash}~{STATUS})") (class "Default")
      (node (ref "IC5") (pin "136") (pinfunction "GPIO136/~{STATUS}_136") (pintype "bidirectional"))
      (node (ref "R5") (pin "2") (pinfunction "2_2") (pintype "passive"))
    )
    (net (code "125") (name "Net-(IC5I-GPIO138{slash}CONF_DONE)") (class "Default")
      (node (ref "IC5") (pin "138") (pinfunction "GPIO138/CONF_DONE_138") (pintype "bidirectional"))
      (node (ref "R6") (pin "2") (pinfunction "2_2") (pintype "passive"))
    )
    (net (code "126") (name "Net-(IC6-VBAT)") (class "Default")
      (node (ref "BAT1") (pin "+@1") (pinfunction "+_+@1") (pintype "power_in"))
      (node (ref "BAT1") (pin "+@2") (pinfunction "+_+@2") (pintype "power_in"))
      (node (ref "BAT1") (pin "+@3") (pinfunction "+_+@3") (pintype "power_in"))
      (node (ref "BAT1") (pin "+@4") (pinfunction "+_+@4") (pintype "power_in"))
      (node (ref "IC6") (pin "6") (pinfunction "VBAT_6") (pintype "power_in"))
    )
    (net (code "127") (name "Net-(IC7-SW)") (class "Default")
      (node (ref "C4") (pin "2") (pinfunction "2_2") (pintype "passive"))
      (node (ref "IC7") (pin "2") (pinfunction "SW_2") (pintype "power_in"))
      (node (ref "L2") (pin "1") (pinfunction "1_1") (pintype "passive"))
    )
    (net (code "128") (name "Net-(IC7-VBST)") (class "Default")
      (node (ref "C4") (pin "1") (pinfunction "1_1") (pintype "passive"))
      (node (ref "IC7") (pin "6") (pinfunction "VBST_6") (pintype "passive"))
    )
    (net (code "129") (name "Net-(IC7-VFB)") (class "Default")
      (node (ref "IC7") (pin "4") (pinfunction "VFB_4") (pintype "passive"))
      (node (ref "R1") (pin "2") (pinfunction "2_2") (pintype "passive"))
      (node (ref "R2") (pin "1") (pinfunction "1_1") (pintype "passive"))
    )
    (net (code "130") (name "Net-(IC10-SCL)") (class "Default")
      (node (ref "IC10") (pin "6") (pinfunction "SCL_6") (pintype "input"))
      (node (ref "R17") (pin "2") (pinfunction "2_2") (pintype "passive"))
      (node (ref "RP1") (pin "28") (pinfunction "ID_SC_28") (pintype "bidirectional"))
    )
    (net (code "131") (name "Net-(IC10-SDA)") (class "Default")
      (node (ref "IC10") (pin "5") (pinfunction "SDA_5") (pintype "bidirectional"))
      (node (ref "R18") (pin "1") (pinfunction "1_1") (pintype "passive"))
      (node (ref "RP1") (pin "27") (pinfunction "ID_SD_27") (pintype "bidirectional"))
    )
    (net (code "132") (name "Net-(IC10-WP)") (class "Default")
      (node (ref "IC10") (pin "7") (pinfunction "WP_7") (pintype "input"))
      (node (ref "R16") (pin "1") (pinfunction "1_1") (pintype "passive"))
    )
    (net (code "133") (name "Net-(IC11-EN)") (class "Default")
      (node (ref "C19") (pin "2") (pinfunction "2_2") (pintype "passive"))
      (node (ref "IC11") (pin "1") (pinfunction "VINA_1") (pintype "input"))
      (node (ref "IC11") (pin "12") (pinfunction "EN_12") (pintype "input"))
    )
    (net (code "134") (name "Net-(IC11-FB)") (class "Default")
      (node (ref "IC11") (pin "3") (pinfunction "FB_3") (pintype "input"))
      (node (ref "R20") (pin "2") (pinfunction "2_2") (pintype "passive"))
      (node (ref "R21") (pin "1") (pinfunction "1_1") (pintype "passive"))
    )
    (net (code "135") (name "Net-(IC11-L1-Pad8)") (class "Default")
      (node (ref "IC11") (pin "8") (pinfunction "L1_8") (pintype "input"))
      (node (ref "IC11") (pin "9") (pinfunction "L1_9") (pintype "input"))
      (node (ref "L1") (pin "1") (pinfunction "1_1") (pintype "passive"))
    )
    (net (code "136") (name "Net-(IC11-L2-Pad6)") (class "Default")
      (node (ref "IC11") (pin "6") (pinfunction "L2_6") (pintype "input"))
      (node (ref "IC11") (pin "7") (pinfunction "L2_7") (pintype "input"))
      (node (ref "L1") (pin "2") (pinfunction "2_2") (pintype "passive"))
    )
    (net (code "137") (name "Net-(RP1-SCL)") (class "Default")
      (node (ref "RASP_I2C") (pin "3") (pinfunction "3_3") (pintype "passive"))
      (node (ref "RP1") (pin "5") (pinfunction "SCL_5") (pintype "bidirectional"))
    )
    (net (code "138") (name "Net-(RP1-SDA)") (class "Default")
      (node (ref "RASP_I2C") (pin "4") (pinfunction "4_4") (pintype "passive"))
      (node (ref "RP1") (pin "3") (pinfunction "SDA_3") (pintype "bidirectional"))
    )
    (net (code "139") (name "OE") (class "Default")
      (node (ref "IC4") (pin "41") (pinfunction "~{OE}_41") (pintype "input"))
      (node (ref "IC5") (pin "113") (pinfunction "GPIO113_113") (pintype "bidirectional"))
    )
    (net (code "140") (name "RPI_IRQ") (class "Default")
      (node (ref "IC5") (pin "80") (pinfunction "GPIO80/VREFB5N0_80") (pintype "bidirectional"))
      (node (ref "RP1") (pin "22") (pinfunction "GPIO25_22") (pintype "bidirectional"))
    )
    (net (code "141") (name "SCE") (class "Default")
      (node (ref "IC5") (pin "61") (pinfunction "GPIO61/VREFB4N0_61") (pintype "bidirectional"))
      (node (ref "RP1") (pin "24") (pinfunction "CE0_24") (pintype "bidirectional"))
    )
    (net (code "142") (name "SCLK") (class "Default")
      (node (ref "IC5") (pin "58") (pinfunction "GPIO58_58") (pintype "bidirectional"))
      (node (ref "RP1") (pin "23") (pinfunction "SCLK_23") (pintype "bidirectional"))
    )
    (net (code "143") (name "SRA0") (class "Default")
      (node (ref "IC4") (pin "1") (pinfunction "A0_1") (pintype "input"))
      (node (ref "IC5") (pin "106") (pinfunction "GPIO106_106") (pintype "bidirectional"))
    )
    (net (code "144") (name "SRA1") (class "Default")
      (node (ref "IC4") (pin "2") (pinfunction "A1_2") (pintype "input"))
      (node (ref "IC5") (pin "105") (pinfunction "GPIO105_105") (pintype "bidirectional"))
    )
    (net (code "145") (name "SRA2") (class "Default")
      (node (ref "IC4") (pin "3") (pinfunction "A2_3") (pintype "input"))
      (node (ref "IC5") (pin "102") (pinfunction "GPIO102_102") (pintype "bidirectional"))
    )
    (net (code "146") (name "SRA3") (class "Default")
      (node (ref "IC4") (pin "4") (pinfunction "A3_4") (pintype "input"))
      (node (ref "IC5") (pin "101") (pinfunction "GPIO101_101") (pintype "bidirectional"))
    )
    (net (code "147") (name "SRA4") (class "Default")
      (node (ref "IC4") (pin "5") (pinfunction "A4_5") (pintype "input"))
      (node (ref "IC5") (pin "100") (pinfunction "GPIO100_100") (pintype "bidirectional"))
    )
    (net (code "148") (name "SRA5") (class "Default")
      (node (ref "IC4") (pin "18") (pinfunction "A5_18") (pintype "input"))
      (node (ref "IC5") (pin "87") (pinfunction "GPIO87_87") (pintype "bidirectional"))
    )
    (net (code "149") (name "SRA6") (class "Default")
      (node (ref "IC4") (pin "19") (pinfunction "A6_19") (pintype "input"))
      (node (ref "IC5") (pin "86") (pinfunction "GPIO86_86") (pintype "bidirectional"))
    )
    (net (code "150") (name "SRA7") (class "Default")
      (node (ref "IC4") (pin "20") (pinfunction "A7_20") (pintype "input"))
      (node (ref "IC5") (pin "85") (pinfunction "GPIO85_85") (pintype "bidirectional"))
    )
    (net (code "151") (name "SRA8") (class "Default")
      (node (ref "IC4") (pin "21") (pinfunction "A8_21") (pintype "input"))
      (node (ref "IC5") (pin "84") (pinfunction "GPIO84_84") (pintype "bidirectional"))
    )
    (net (code "152") (name "SRA9") (class "Default")
      (node (ref "IC4") (pin "22") (pinfunction "A9_22") (pintype "input"))
      (node (ref "IC5") (pin "81") (pinfunction "GPIO81_81") (pintype "bidirectional"))
    )
    (net (code "153") (name "SRA10") (class "Default")
      (node (ref "IC4") (pin "23") (pinfunction "A10_23") (pintype "input"))
      (node (ref "IC5") (pin "59") (pinfunction "GPIO59_59") (pintype "bidirectional"))
    )
    (net (code "154") (name "SRA11") (class "Default")
      (node (ref "IC4") (pin "24") (pinfunction "A11_24") (pintype "input"))
      (node (ref "IC5") (pin "60") (pinfunction "GPIO60_60") (pintype "bidirectional"))
    )
    (net (code "155") (name "SRA12") (class "Default")
      (node (ref "IC4") (pin "25") (pinfunction "A12_25") (pintype "input"))
      (node (ref "IC5") (pin "62") (pinfunction "GPIO62_62") (pintype "bidirectional"))
    )
    (net (code "156") (name "SRA13") (class "Default")
      (node (ref "IC4") (pin "26") (pinfunction "A13_26") (pintype "input"))
      (node (ref "IC5") (pin "64") (pinfunction "GPIO64_64") (pintype "bidirectional"))
    )
    (net (code "157") (name "SRA14") (class "Default")
      (node (ref "IC4") (pin "27") (pinfunction "A14_27") (pintype "input"))
      (node (ref "IC5") (pin "65") (pinfunction "GPIO65_65") (pintype "bidirectional"))
    )
    (net (code "158") (name "SRA15") (class "Default")
      (node (ref "IC4") (pin "42") (pinfunction "A15_42") (pintype "input"))
      (node (ref "IC5") (pin "114") (pinfunction "GPIO114_114") (pintype "bidirectional"))
    )
    (net (code "159") (name "SRA16") (class "Default")
      (node (ref "IC4") (pin "43") (pinfunction "A16_43") (pintype "input"))
      (node (ref "IC5") (pin "118") (pinfunction "GPIO118_118") (pintype "bidirectional"))
    )
    (net (code "160") (name "SRA17") (class "Default")
      (node (ref "IC4") (pin "44") (pinfunction "A17_44") (pintype "input"))
      (node (ref "IC5") (pin "119") (pinfunction "GPIO119_119") (pintype "bidirectional"))
    )
    (net (code "161") (name "SRA18") (class "Default")
      (node (ref "IC4") (pin "28") (pinfunction "A18_28") (pintype "input"))
      (node (ref "IC5") (pin "66") (pinfunction "GPIO66_66") (pintype "bidirectional"))
    )
    (net (code "162") (name "SRD0") (class "Default")
      (node (ref "IC4") (pin "7") (pinfunction "D0_7") (pintype "bidirectional"))
      (node (ref "IC5") (pin "99") (pinfunction "GPIO99_99") (pintype "bidirectional"))
    )
    (net (code "163") (name "SRD1") (class "Default")
      (node (ref "IC4") (pin "8") (pinfunction "D1_8") (pintype "bidirectional"))
      (node (ref "IC5") (pin "98") (pinfunction "GPIO98/DPCLK2_98") (pintype "bidirectional"))
    )
    (net (code "164") (name "SRD2") (class "Default")
      (node (ref "IC4") (pin "9") (pinfunction "D2_9") (pintype "bidirectional"))
      (node (ref "IC5") (pin "96") (pinfunction "GPIO96/DPCLK3_96") (pintype "bidirectional"))
    )
    (net (code "165") (name "SRD3") (class "Default")
      (node (ref "IC4") (pin "10") (pinfunction "D3_10") (pintype "bidirectional"))
      (node (ref "IC5") (pin "93") (pinfunction "GPIO93_93") (pintype "bidirectional"))
    )
    (net (code "166") (name "SRD4") (class "Default")
      (node (ref "IC4") (pin "13") (pinfunction "D4_13") (pintype "bidirectional"))
      (node (ref "IC5") (pin "92") (pinfunction "GPIO92_92") (pintype "bidirectional"))
    )
    (net (code "167") (name "SRD5") (class "Default")
      (node (ref "IC4") (pin "14") (pinfunction "D5_14") (pintype "bidirectional"))
      (node (ref "IC5") (pin "91") (pinfunction "GPIO91/CLK3N_91") (pintype "bidirectional"))
    )
    (net (code "168") (name "SRD6") (class "Default")
      (node (ref "IC4") (pin "15") (pinfunction "D6_15") (pintype "bidirectional"))
      (node (ref "IC5") (pin "90") (pinfunction "GPIO90/CLK3P_90") (pintype "bidirectional"))
    )
    (net (code "169") (name "SRD7") (class "Default")
      (node (ref "IC4") (pin "16") (pinfunction "D7_16") (pintype "bidirectional"))
      (node (ref "IC5") (pin "89") (pinfunction "GPIO89/CLK2N_89") (pintype "bidirectional"))
    )
    (net (code "170") (name "SRD8") (class "Default")
      (node (ref "IC4") (pin "29") (pinfunction "D8_29") (pintype "bidirectional"))
      (node (ref "IC5") (pin "69") (pinfunction "GPIO69_69") (pintype "bidirectional"))
    )
    (net (code "171") (name "SRD9") (class "Default")
      (node (ref "IC4") (pin "30") (pinfunction "D9_30") (pintype "bidirectional"))
      (node (ref "IC5") (pin "70") (pinfunction "GPIO70_70") (pintype "bidirectional"))
    )
    (net (code "172") (name "SRD10") (class "Default")
      (node (ref "IC4") (pin "31") (pinfunction "D10_31") (pintype "bidirectional"))
      (node (ref "IC5") (pin "74") (pinfunction "GPIO74_74") (pintype "bidirectional"))
    )
    (net (code "173") (name "SRD11") (class "Default")
      (node (ref "IC4") (pin "32") (pinfunction "D11_32") (pintype "bidirectional"))
      (node (ref "IC5") (pin "75") (pinfunction "GPIO75_75") (pintype "bidirectional"))
    )
    (net (code "174") (name "SRD12") (class "Default")
      (node (ref "IC4") (pin "35") (pinfunction "D12_35") (pintype "bidirectional"))
      (node (ref "IC5") (pin "76") (pinfunction "GPIO76_76") (pintype "bidirectional"))
    )
    (net (code "175") (name "SRD13") (class "Default")
      (node (ref "IC4") (pin "36") (pinfunction "D13_36") (pintype "bidirectional"))
      (node (ref "IC5") (pin "77") (pinfunction "GPIO77_77") (pintype "bidirectional"))
    )
    (net (code "176") (name "SRD14") (class "Default")
      (node (ref "IC4") (pin "37") (pinfunction "D14_37") (pintype "bidirectional"))
      (node (ref "IC5") (pin "78") (pinfunction "GPIO78_78") (pintype "bidirectional"))
    )
    (net (code "177") (name "SRD15") (class "Default")
      (node (ref "IC4") (pin "38") (pinfunction "D15_38") (pintype "bidirectional"))
      (node (ref "IC5") (pin "79") (pinfunction "GPIO79_79") (pintype "bidirectional"))
    )
    (net (code "178") (name "TCK") (class "Default")
      (node (ref "IC5") (pin "18") (pinfunction "GPIO18/TCK_18") (pintype "bidirectional"))
      (node (ref "JTAG") (pin "1") (pinfunction "1_1") (pintype "passive"))
      (node (ref "R10") (pin "2") (pinfunction "2_2") (pintype "passive"))
    )
    (net (code "179") (name "TDI") (class "Default")
      (node (ref "IC5") (pin "19") (pinfunction "GPIO19/TDI_19") (pintype "bidirectional"))
      (node (ref "JTAG") (pin "9") (pinfunction "9_9") (pintype "passive"))
      (node (ref "R9") (pin "1") (pinfunction "1_1") (pintype "passive"))
    )
    (net (code "180") (name "TDO") (class "Default")
      (node (ref "IC5") (pin "20") (pinfunction "GPIO20/TDO_20") (pintype "bidirectional"))
      (node (ref "JTAG") (pin "3") (pinfunction "3_3") (pintype "passive"))
    )
    (net (code "181") (name "TMS") (class "Default")
      (node (ref "IC5") (pin "16") (pinfunction "GPIO16/TMS_16") (pintype "bidirectional"))
      (node (ref "JTAG") (pin "5") (pinfunction "5_5") (pintype "passive"))
      (node (ref "R8") (pin "1") (pinfunction "1_1") (pintype "passive"))
    )
    (net (code "182") (name "UB") (class "Default")
      (node (ref "IC4") (pin "40") (pinfunction "~{UB}_40") (pintype "input"))
      (node (ref "IC5") (pin "111") (pinfunction "GPIO111_111") (pintype "bidirectional"))
    )
    (net (code "183") (name "VCC{slash}2") (class "Default")
      (node (ref "C8") (pin "1") (pinfunction "1_1") (pintype "passive"))
      (node (ref "IC10") (pin "8") (pinfunction "VCC_8") (pintype "power_in"))
      (node (ref "R16") (pin "2") (pinfunction "2_2") (pintype "passive"))
      (node (ref "R17") (pin "1") (pinfunction "1_1") (pintype "passive"))
      (node (ref "R18") (pin "2") (pinfunction "2_2") (pintype "passive"))
      (node (ref "RP1") (pin "1") (pinfunction "3V3_1") (pintype "power_in"))
      (node (ref "RP1") (pin "17") (pinfunction "3V3_17") (pintype "power_in"))
    )
    (net (code "184") (name "WE") (class "Default")
      (node (ref "IC4") (pin "17") (pinfunction "~{WE}_17") (pintype "input"))
      (node (ref "IC5") (pin "88") (pinfunction "GPIO88/CLK2P_88") (pintype "bidirectional"))
    )
    (net (code "185") (name "unconnected-(IC2A-A2-Pad46)") (class "Default")
      (node (ref "IC2") (pin "46") (pinfunction "A2_46") (pintype "bidirectional"))
    )
    (net (code "186") (name "unconnected-(IC3C-B3-Pad16)") (class "Default")
      (node (ref "IC3") (pin "16") (pinfunction "B3_16") (pintype "bidirectional"))
    )
    (net (code "187") (name "unconnected-(IC3D-A1-Pad30)") (class "Default")
      (node (ref "IC3") (pin "30") (pinfunction "A1_30") (pintype "bidirectional"))
    )
    (net (code "188") (name "unconnected-(IC3D-A2-Pad29)") (class "Default")
      (node (ref "IC3") (pin "29") (pinfunction "A2_29") (pintype "bidirectional"))
    )
    (net (code "189") (name "unconnected-(IC3D-A3-Pad27)") (class "Default")
      (node (ref "IC3") (pin "27") (pinfunction "A3_27") (pintype "bidirectional"))
    )
    (net (code "190") (name "unconnected-(IC3D-A4-Pad26)") (class "Default")
      (node (ref "IC3") (pin "26") (pinfunction "A4_26") (pintype "bidirectional"))
    )
    (net (code "191") (name "unconnected-(IC3D-B1-Pad19)") (class "Default")
      (node (ref "IC3") (pin "19") (pinfunction "B1_19") (pintype "bidirectional"))
    )
    (net (code "192") (name "unconnected-(IC3D-B2-Pad20)") (class "Default")
      (node (ref "IC3") (pin "20") (pinfunction "B2_20") (pintype "bidirectional"))
    )
    (net (code "193") (name "unconnected-(IC3D-B3-Pad22)") (class "Default")
      (node (ref "IC3") (pin "22") (pinfunction "B3_22") (pintype "bidirectional"))
    )
    (net (code "194") (name "unconnected-(IC3D-B4-Pad23)") (class "Default")
      (node (ref "IC3") (pin "23") (pinfunction "B4_23") (pintype "bidirectional"))
    )
    (net (code "195") (name "unconnected-(IC5B-GPIO17{slash}VREFB1N0-Pad17)") (class "Default")
      (node (ref "IC5") (pin "17") (pinfunction "GPIO17/VREFB1N0_17") (pintype "bidirectional"))
    )
    (net (code "196") (name "unconnected-(IC5B-GPIO25-Pad25)") (class "Default")
      (node (ref "IC5") (pin "25") (pinfunction "GPIO25_25") (pintype "bidirectional"))
    )
    (net (code "197") (name "unconnected-(IC5C-GPIO27{slash}CLK0P-Pad27)") (class "Default")
      (node (ref "IC5") (pin "27") (pinfunction "GPIO27/CLK0P_27") (pintype "bidirectional"))
    )
    (net (code "198") (name "unconnected-(IC5C-GPIO30{slash}VREFB2N0-Pad30)") (class "Default")
      (node (ref "IC5") (pin "30") (pinfunction "GPIO30/VREFB2N0_30") (pintype "bidirectional"))
    )
    (net (code "199") (name "unconnected-(IC5I-GPIO123{slash}VREFB8N0-Pad123)") (class "Default")
      (node (ref "IC5") (pin "123") (pinfunction "GPIO123/VREFB8N0_123") (pintype "bidirectional"))
    )
    (net (code "200") (name "unconnected-(IC6-32KHZ-Pad1)") (class "Default")
      (node (ref "IC6") (pin "1") (pinfunction "32KHZ_1") (pintype "output"))
    )
    (net (code "201") (name "unconnected-(IC6-~{INT}{slash}SQW-Pad3)") (class "Default")
      (node (ref "IC6") (pin "3") (pinfunction "~{INT}/SQW_3") (pintype "output"))
    )
    (net (code "202") (name "unconnected-(IC6-~{RST}-Pad4)") (class "Default")
      (node (ref "IC6") (pin "4") (pinfunction "~{RST}_4") (pintype "input"))
    )
    (net (code "203") (name "unconnected-(IC8-CLKREF-Pad4)") (class "Default")
      (node (ref "IC8") (pin "4") (pinfunction "CLKREF_4") (pintype "output"))
    )
    (net (code "204") (name "unconnected-(IC8-X2-Pad8)") (class "Default")
      (node (ref "IC8") (pin "8") (pinfunction "X2_8") (pintype "input"))
    )
    (net (code "205") (name "unconnected-(IC9-NC{slash}FB-Pad4)") (class "Default")
      (node (ref "IC9") (pin "4") (pinfunction "NC/FB_4") (pintype "passive"))
    )
    (net (code "206") (name "unconnected-(IC11-PG-Pad14)") (class "Default")
      (node (ref "IC11") (pin "14") (pinfunction "PG_14") (pintype "output"))
    )
    (net (code "207") (name "unconnected-(JTAG-Pad6)") (class "Default")
      (node (ref "JTAG") (pin "6") (pinfunction "6_6") (pintype "passive"))
    )
    (net (code "208") (name "unconnected-(JTAG-Pad7)") (class "Default")
      (node (ref "JTAG") (pin "7") (pinfunction "7_7") (pintype "passive"))
    )
    (net (code "209") (name "unconnected-(JTAG-Pad8)") (class "Default")
      (node (ref "JTAG") (pin "8") (pinfunction "8_8") (pintype "passive"))
    )
    (net (code "210") (name "unconnected-(RP1-CE0-Pad36)") (class "Default")
      (node (ref "RP1") (pin "36") (pinfunction "CE0_36") (pintype "bidirectional"))
    )
    (net (code "211") (name "unconnected-(RP1-CE1-Pad26)") (class "Default")
      (node (ref "RP1") (pin "26") (pinfunction "CE1_26") (pintype "bidirectional"))
    )
    (net (code "212") (name "unconnected-(RP1-GPIO04-Pad7)") (class "Default")
      (node (ref "RP1") (pin "7") (pinfunction "GPIO04_7") (pintype "bidirectional"))
    )
    (net (code "213") (name "unconnected-(RP1-GPIO05-Pad29)") (class "Default")
      (node (ref "RP1") (pin "29") (pinfunction "GPIO05_29") (pintype "bidirectional"))
    )
    (net (code "214") (name "unconnected-(RP1-GPIO06-Pad31)") (class "Default")
      (node (ref "RP1") (pin "31") (pinfunction "GPIO06_31") (pintype "bidirectional"))
    )
    (net (code "215") (name "unconnected-(RP1-GPIO12-Pad32)") (class "Default")
      (node (ref "RP1") (pin "32") (pinfunction "GPIO12_32") (pintype "bidirectional"))
    )
    (net (code "216") (name "unconnected-(RP1-GPIO13-Pad33)") (class "Default")
      (node (ref "RP1") (pin "33") (pinfunction "GPIO13_33") (pintype "bidirectional"))
    )
    (net (code "217") (name "unconnected-(RP1-GPIO17-Pad11)") (class "Default")
      (node (ref "RP1") (pin "11") (pinfunction "GPIO17_11") (pintype "bidirectional"))
    )
    (net (code "218") (name "unconnected-(RP1-GPIO18-Pad12)") (class "Default")
      (node (ref "RP1") (pin "12") (pinfunction "GPIO18_12") (pintype "bidirectional"))
    )
    (net (code "219") (name "unconnected-(RP1-GPIO22-Pad15)") (class "Default")
      (node (ref "RP1") (pin "15") (pinfunction "GPIO22_15") (pintype "bidirectional"))
    )
    (net (code "220") (name "unconnected-(RP1-GPIO23-Pad16)") (class "Default")
      (node (ref "RP1") (pin "16") (pinfunction "GPIO23_16") (pintype "bidirectional"))
    )
    (net (code "221") (name "unconnected-(RP1-GPIO24-Pad18)") (class "Default")
      (node (ref "RP1") (pin "18") (pinfunction "GPIO24_18") (pintype "bidirectional"))
    )
    (net (code "222") (name "unconnected-(RP1-GPIO26-Pad37)") (class "Default")
      (node (ref "RP1") (pin "37") (pinfunction "GPIO26_37") (pintype "bidirectional"))
    )
    (net (code "223") (name "unconnected-(RP1-GPIO27-Pad13)") (class "Default")
      (node (ref "RP1") (pin "13") (pinfunction "GPIO27_13") (pintype "bidirectional"))
    )
    (net (code "224") (name "unconnected-(RP1-MISO-Pad35)") (class "Default")
      (node (ref "RP1") (pin "35") (pinfunction "MISO_35") (pintype "bidirectional"))
    )
    (net (code "225") (name "unconnected-(RP1-MOSI-Pad38)") (class "Default")
      (node (ref "RP1") (pin "38") (pinfunction "MOSI_38") (pintype "bidirectional"))
    )
    (net (code "226") (name "unconnected-(RP1-RXD-Pad10)") (class "Default")
      (node (ref "RP1") (pin "10") (pinfunction "RXD_10") (pintype "bidirectional"))
    )
    (net (code "227") (name "unconnected-(RP1-SCLK-Pad40)") (class "Default")
      (node (ref "RP1") (pin "40") (pinfunction "SCLK_40") (pintype "bidirectional"))
    )
    (net (code "228") (name "unconnected-(RP1-TXD-Pad8)") (class "Default")
      (node (ref "RP1") (pin "8") (pinfunction "TXD_8") (pintype "bidirectional"))
    )
  )
)
